# Led_panel_v2_0.net
KiCad netlist of a schematic drawn in EAGLE
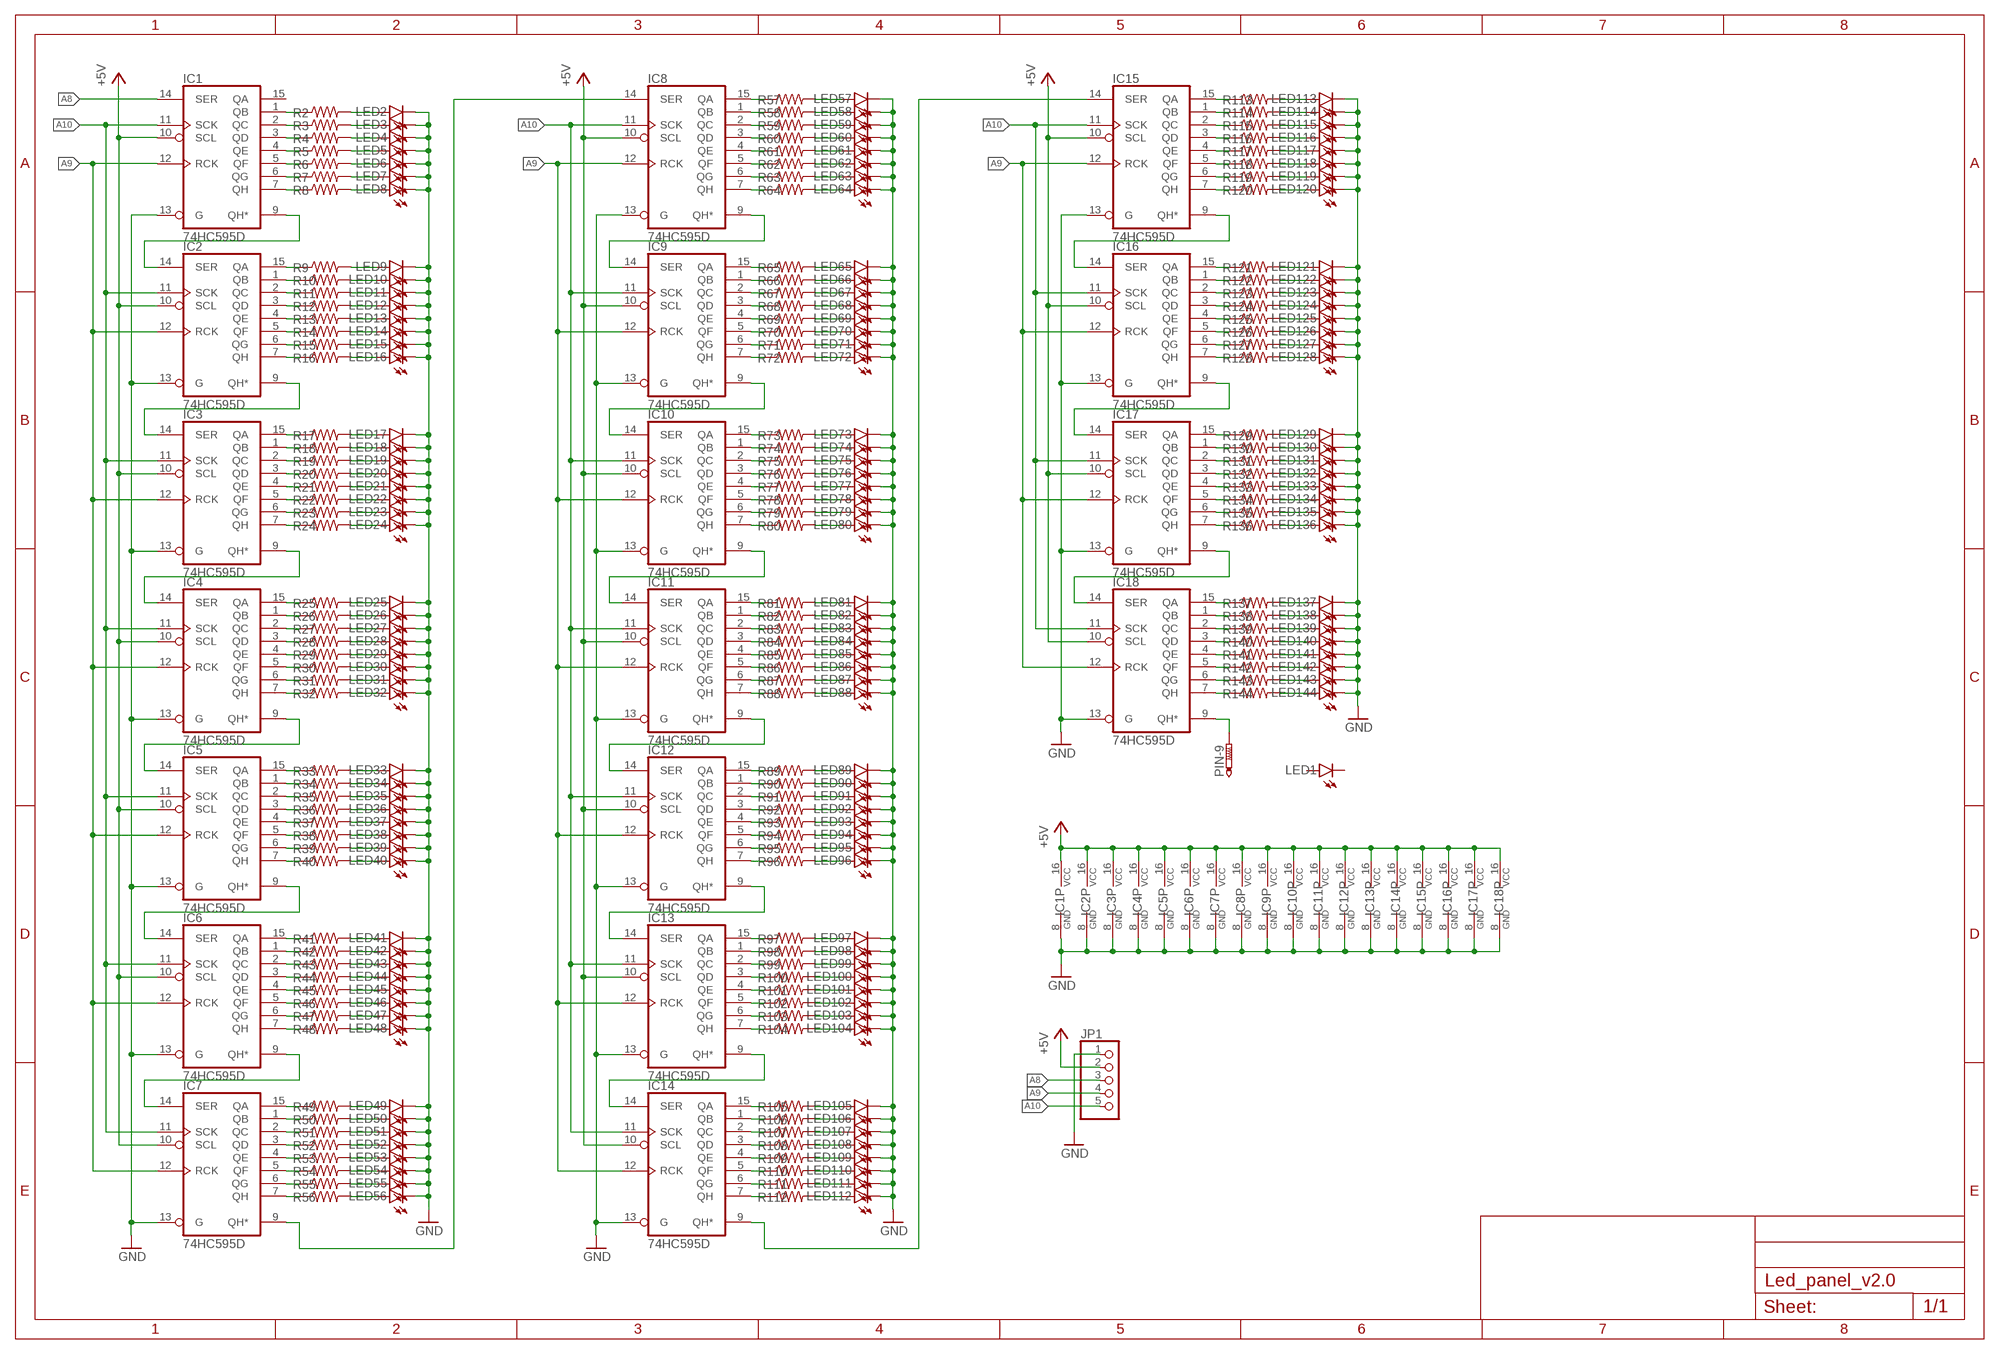
[diagram p0: schematic, sheet 1]

(export (version "E")
  (design (tool "Eeschema 10.0.6"))
  (components
    (comp (ref "IC1")
      (value "74HC595D")
      (footprint "eagle-import:SO16")
      (libsource (lib "eagle-import") (part "74595DHC"))
    )
    (comp (ref "IC2")
      (value "74HC595D")
      (footprint "eagle-import:SO16")
      (libsource (lib "eagle-import") (part "74595DHC"))
    )
    (comp (ref "IC3")
      (value "74HC595D")
      (footprint "eagle-import:SO16")
      (libsource (lib "eagle-import") (part "74595DHC"))
    )
    (comp (ref "IC4")
      (value "74HC595D")
      (footprint "eagle-import:SO16")
      (libsource (lib "eagle-import") (part "74595DHC"))
    )
    (comp (ref "IC5")
      (value "74HC595D")
      (footprint "eagle-import:SO16")
      (libsource (lib "eagle-import") (part "74595DHC"))
    )
    (comp (ref "IC6")
      (value "74HC595D")
      (footprint "eagle-import:SO16")
      (libsource (lib "eagle-import") (part "74595DHC"))
    )
    (comp (ref "IC7")
      (value "74HC595D")
      (footprint "eagle-import:SO16")
      (libsource (lib "eagle-import") (part "74595DHC"))
    )
    (comp (ref "IC8")
      (value "74HC595D")
      (footprint "eagle-import:SO16")
      (libsource (lib "eagle-import") (part "74595DHC"))
    )
    (comp (ref "IC9")
      (value "74HC595D")
      (footprint "eagle-import:SO16")
      (libsource (lib "eagle-import") (part "74595DHC"))
    )
    (comp (ref "IC10")
      (value "74HC595D")
      (footprint "eagle-import:SO16")
      (libsource (lib "eagle-import") (part "74595DHC"))
    )
    (comp (ref "IC11")
      (value "74HC595D")
      (footprint "eagle-import:SO16")
      (libsource (lib "eagle-import") (part "74595DHC"))
    )
    (comp (ref "IC12")
      (value "74HC595D")
      (footprint "eagle-import:SO16")
      (libsource (lib "eagle-import") (part "74595DHC"))
    )
    (comp (ref "IC13")
      (value "74HC595D")
      (footprint "eagle-import:SO16")
      (libsource (lib "eagle-import") (part "74595DHC"))
    )
    (comp (ref "IC14")
      (value "74HC595D")
      (footprint "eagle-import:SO16")
      (libsource (lib "eagle-import") (part "74595DHC"))
    )
    (comp (ref "IC15")
      (value "74HC595D")
      (footprint "eagle-import:SO16")
      (libsource (lib "eagle-import") (part "74595DHC"))
    )
    (comp (ref "IC16")
      (value "74HC595D")
      (footprint "eagle-import:SO16")
      (libsource (lib "eagle-import") (part "74595DHC"))
    )
    (comp (ref "IC17")
      (value "74HC595D")
      (footprint "eagle-import:SO16")
      (libsource (lib "eagle-import") (part "74595DHC"))
    )
    (comp (ref "IC18")
      (value "74HC595D")
      (footprint "eagle-import:SO16")
      (libsource (lib "eagle-import") (part "74595DHC"))
    )
    (comp (ref "JP1")
      (value "PINHD-1X5")
      (footprint "eagle-import:1X05")
      (libsource (lib "eagle-import") (part "PINHD-1X5"))
    )
    (comp (ref "LED1")
      (value "LED3MM")
      (footprint "eagle-import:LED3MM")
      (libsource (lib "eagle-import") (part "LED3MM"))
    )
    (comp (ref "LED2")
      (value "LED3MM")
      (footprint "eagle-import:LED3MM")
      (libsource (lib "eagle-import") (part "LED3MM"))
    )
    (comp (ref "LED3")
      (value "LED3MM")
      (footprint "eagle-import:LED3MM")
      (libsource (lib "eagle-import") (part "LED3MM"))
    )
    (comp (ref "LED4")
      (value "LED3MM")
      (footprint "eagle-import:LED3MM")
      (libsource (lib "eagle-import") (part "LED3MM"))
    )
    (comp (ref "LED5")
      (value "LED3MM")
      (footprint "eagle-import:LED3MM")
      (libsource (lib "eagle-import") (part "LED3MM"))
    )
    (comp (ref "LED6")
      (value "LED3MM")
      (footprint "eagle-import:LED3MM")
      (libsource (lib "eagle-import") (part "LED3MM"))
    )
    (comp (ref "LED7")
      (value "LED3MM")
      (footprint "eagle-import:LED3MM")
      (libsource (lib "eagle-import") (part "LED3MM"))
    )
    (comp (ref "LED8")
      (value "LED3MM")
      (footprint "eagle-import:LED3MM")
      (libsource (lib "eagle-import") (part "LED3MM"))
    )
    (comp (ref "LED9")
      (value "LED3MM")
      (footprint "eagle-import:LED3MM")
      (libsource (lib "eagle-import") (part "LED3MM"))
    )
    (comp (ref "LED10")
      (value "LED3MM")
      (footprint "eagle-import:LED3MM")
      (libsource (lib "eagle-import") (part "LED3MM"))
    )
    (comp (ref "LED11")
      (value "LED3MM")
      (footprint "eagle-import:LED3MM")
      (libsource (lib "eagle-import") (part "LED3MM"))
    )
    (comp (ref "LED12")
      (value "LED3MM")
      (footprint "eagle-import:LED3MM")
      (libsource (lib "eagle-import") (part "LED3MM"))
    )
    (comp (ref "LED13")
      (value "LED3MM")
      (footprint "eagle-import:LED3MM")
      (libsource (lib "eagle-import") (part "LED3MM"))
    )
    (comp (ref "LED14")
      (value "LED3MM")
      (footprint "eagle-import:LED3MM")
      (libsource (lib "eagle-import") (part "LED3MM"))
    )
    (comp (ref "LED15")
      (value "LED3MM")
      (footprint "eagle-import:LED3MM")
      (libsource (lib "eagle-import") (part "LED3MM"))
    )
    (comp (ref "LED16")
      (value "LED3MM")
      (footprint "eagle-import:LED3MM")
      (libsource (lib "eagle-import") (part "LED3MM"))
    )
    (comp (ref "LED17")
      (value "LED3MM")
      (footprint "eagle-import:LED3MM")
      (libsource (lib "eagle-import") (part "LED3MM"))
    )
    (comp (ref "LED18")
      (value "LED3MM")
      (footprint "eagle-import:LED3MM")
      (libsource (lib "eagle-import") (part "LED3MM"))
    )
    (comp (ref "LED19")
      (value "LED3MM")
      (footprint "eagle-import:LED3MM")
      (libsource (lib "eagle-import") (part "LED3MM"))
    )
    (comp (ref "LED20")
      (value "LED3MM")
      (footprint "eagle-import:LED3MM")
      (libsource (lib "eagle-import") (part "LED3MM"))
    )
    (comp (ref "LED21")
      (value "LED3MM")
      (footprint "eagle-import:LED3MM")
      (libsource (lib "eagle-import") (part "LED3MM"))
    )
    (comp (ref "LED22")
      (value "LED3MM")
      (footprint "eagle-import:LED3MM")
      (libsource (lib "eagle-import") (part "LED3MM"))
    )
    (comp (ref "LED23")
      (value "LED3MM")
      (footprint "eagle-import:LED3MM")
      (libsource (lib "eagle-import") (part "LED3MM"))
    )
    (comp (ref "LED24")
      (value "LED3MM")
      (footprint "eagle-import:LED3MM")
      (libsource (lib "eagle-import") (part "LED3MM"))
    )
    (comp (ref "LED25")
      (value "LED3MM")
      (footprint "eagle-import:LED3MM")
      (libsource (lib "eagle-import") (part "LED3MM"))
    )
    (comp (ref "LED26")
      (value "LED3MM")
      (footprint "eagle-import:LED3MM")
      (libsource (lib "eagle-import") (part "LED3MM"))
    )
    (comp (ref "LED27")
      (value "LED3MM")
      (footprint "eagle-import:LED3MM")
      (libsource (lib "eagle-import") (part "LED3MM"))
    )
    (comp (ref "LED28")
      (value "LED3MM")
      (footprint "eagle-import:LED3MM")
      (libsource (lib "eagle-import") (part "LED3MM"))
    )
    (comp (ref "LED29")
      (value "LED3MM")
      (footprint "eagle-import:LED3MM")
      (libsource (lib "eagle-import") (part "LED3MM"))
    )
    (comp (ref "LED30")
      (value "LED3MM")
      (footprint "eagle-import:LED3MM")
      (libsource (lib "eagle-import") (part "LED3MM"))
    )
    (comp (ref "LED31")
      (value "LED3MM")
      (footprint "eagle-import:LED3MM")
      (libsource (lib "eagle-import") (part "LED3MM"))
    )
    (comp (ref "LED32")
      (value "LED3MM")
      (footprint "eagle-import:LED3MM")
      (libsource (lib "eagle-import") (part "LED3MM"))
    )
    (comp (ref "LED33")
      (value "LED3MM")
      (footprint "eagle-import:LED3MM")
      (libsource (lib "eagle-import") (part "LED3MM"))
    )
    (comp (ref "LED34")
      (value "LED3MM")
      (footprint "eagle-import:LED3MM")
      (libsource (lib "eagle-import") (part "LED3MM"))
    )
    (comp (ref "LED35")
      (value "LED3MM")
      (footprint "eagle-import:LED3MM")
      (libsource (lib "eagle-import") (part "LED3MM"))
    )
    (comp (ref "LED36")
      (value "LED3MM")
      (footprint "eagle-import:LED3MM")
      (libsource (lib "eagle-import") (part "LED3MM"))
    )
    (comp (ref "LED37")
      (value "LED3MM")
      (footprint "eagle-import:LED3MM")
      (libsource (lib "eagle-import") (part "LED3MM"))
    )
    (comp (ref "LED38")
      (value "LED3MM")
      (footprint "eagle-import:LED3MM")
      (libsource (lib "eagle-import") (part "LED3MM"))
    )
    (comp (ref "LED39")
      (value "LED3MM")
      (footprint "eagle-import:LED3MM")
      (libsource (lib "eagle-import") (part "LED3MM"))
    )
    (comp (ref "LED40")
      (value "LED3MM")
      (footprint "eagle-import:LED3MM")
      (libsource (lib "eagle-import") (part "LED3MM"))
    )
    (comp (ref "LED41")
      (value "LED3MM")
      (footprint "eagle-import:LED3MM")
      (libsource (lib "eagle-import") (part "LED3MM"))
    )
    (comp (ref "LED42")
      (value "LED3MM")
      (footprint "eagle-import:LED3MM")
      (libsource (lib "eagle-import") (part "LED3MM"))
    )
    (comp (ref "LED43")
      (value "LED3MM")
      (footprint "eagle-import:LED3MM")
      (libsource (lib "eagle-import") (part "LED3MM"))
    )
    (comp (ref "LED44")
      (value "LED3MM")
      (footprint "eagle-import:LED3MM")
      (libsource (lib "eagle-import") (part "LED3MM"))
    )
    (comp (ref "LED45")
      (value "LED3MM")
      (footprint "eagle-import:LED3MM")
      (libsource (lib "eagle-import") (part "LED3MM"))
    )
    (comp (ref "LED46")
      (value "LED3MM")
      (footprint "eagle-import:LED3MM")
      (libsource (lib "eagle-import") (part "LED3MM"))
    )
    (comp (ref "LED47")
      (value "LED3MM")
      (footprint "eagle-import:LED3MM")
      (libsource (lib "eagle-import") (part "LED3MM"))
    )
    (comp (ref "LED48")
      (value "LED3MM")
      (footprint "eagle-import:LED3MM")
      (libsource (lib "eagle-import") (part "LED3MM"))
    )
    (comp (ref "LED49")
      (value "LED3MM")
      (footprint "eagle-import:LED3MM")
      (libsource (lib "eagle-import") (part "LED3MM"))
    )
    (comp (ref "LED50")
      (value "LED3MM")
      (footprint "eagle-import:LED3MM")
      (libsource (lib "eagle-import") (part "LED3MM"))
    )
    (comp (ref "LED51")
      (value "LED3MM")
      (footprint "eagle-import:LED3MM")
      (libsource (lib "eagle-import") (part "LED3MM"))
    )
    (comp (ref "LED52")
      (value "LED3MM")
      (footprint "eagle-import:LED3MM")
      (libsource (lib "eagle-import") (part "LED3MM"))
    )
    (comp (ref "LED53")
      (value "LED3MM")
      (footprint "eagle-import:LED3MM")
      (libsource (lib "eagle-import") (part "LED3MM"))
    )
    (comp (ref "LED54")
      (value "LED3MM")
      (footprint "eagle-import:LED3MM")
      (libsource (lib "eagle-import") (part "LED3MM"))
    )
    (comp (ref "LED55")
      (value "LED3MM")
      (footprint "eagle-import:LED3MM")
      (libsource (lib "eagle-import") (part "LED3MM"))
    )
    (comp (ref "LED56")
      (value "LED3MM")
      (footprint "eagle-import:LED3MM")
      (libsource (lib "eagle-import") (part "LED3MM"))
    )
    (comp (ref "LED57")
      (value "LED3MM")
      (footprint "eagle-import:LED3MM")
      (libsource (lib "eagle-import") (part "LED3MM"))
    )
    (comp (ref "LED58")
      (value "LED3MM")
      (footprint "eagle-import:LED3MM")
      (libsource (lib "eagle-import") (part "LED3MM"))
    )
    (comp (ref "LED59")
      (value "LED3MM")
      (footprint "eagle-import:LED3MM")
      (libsource (lib "eagle-import") (part "LED3MM"))
    )
    (comp (ref "LED60")
      (value "LED3MM")
      (footprint "eagle-import:LED3MM")
      (libsource (lib "eagle-import") (part "LED3MM"))
    )
    (comp (ref "LED61")
      (value "LED3MM")
      (footprint "eagle-import:LED3MM")
      (libsource (lib "eagle-import") (part "LED3MM"))
    )
    (comp (ref "LED62")
      (value "LED3MM")
      (footprint "eagle-import:LED3MM")
      (libsource (lib "eagle-import") (part "LED3MM"))
    )
    (comp (ref "LED63")
      (value "LED3MM")
      (footprint "eagle-import:LED3MM")
      (libsource (lib "eagle-import") (part "LED3MM"))
    )
    (comp (ref "LED64")
      (value "LED3MM")
      (footprint "eagle-import:LED3MM")
      (libsource (lib "eagle-import") (part "LED3MM"))
    )
    (comp (ref "LED65")
      (value "LED3MM")
      (footprint "eagle-import:LED3MM")
      (libsource (lib "eagle-import") (part "LED3MM"))
    )
    (comp (ref "LED66")
      (value "LED3MM")
      (footprint "eagle-import:LED3MM")
      (libsource (lib "eagle-import") (part "LED3MM"))
    )
    (comp (ref "LED67")
      (value "LED3MM")
      (footprint "eagle-import:LED3MM")
      (libsource (lib "eagle-import") (part "LED3MM"))
    )
    (comp (ref "LED68")
      (value "LED3MM")
      (footprint "eagle-import:LED3MM")
      (libsource (lib "eagle-import") (part "LED3MM"))
    )
    (comp (ref "LED69")
      (value "LED3MM")
      (footprint "eagle-import:LED3MM")
      (libsource (lib "eagle-import") (part "LED3MM"))
    )
    (comp (ref "LED70")
      (value "LED3MM")
      (footprint "eagle-import:LED3MM")
      (libsource (lib "eagle-import") (part "LED3MM"))
    )
    (comp (ref "LED71")
      (value "LED3MM")
      (footprint "eagle-import:LED3MM")
      (libsource (lib "eagle-import") (part "LED3MM"))
    )
    (comp (ref "LED72")
      (value "LED3MM")
      (footprint "eagle-import:LED3MM")
      (libsource (lib "eagle-import") (part "LED3MM"))
    )
    (comp (ref "LED73")
      (value "LED3MM")
      (footprint "eagle-import:LED3MM")
      (libsource (lib "eagle-import") (part "LED3MM"))
    )
    (comp (ref "LED74")
      (value "LED3MM")
      (footprint "eagle-import:LED3MM")
      (libsource (lib "eagle-import") (part "LED3MM"))
    )
    (comp (ref "LED75")
      (value "LED3MM")
      (footprint "eagle-import:LED3MM")
      (libsource (lib "eagle-import") (part "LED3MM"))
    )
    (comp (ref "LED76")
      (value "LED3MM")
      (footprint "eagle-import:LED3MM")
      (libsource (lib "eagle-import") (part "LED3MM"))
    )
    (comp (ref "LED77")
      (value "LED3MM")
      (footprint "eagle-import:LED3MM")
      (libsource (lib "eagle-import") (part "LED3MM"))
    )
    (comp (ref "LED78")
      (value "LED3MM")
      (footprint "eagle-import:LED3MM")
      (libsource (lib "eagle-import") (part "LED3MM"))
    )
    (comp (ref "LED79")
      (value "LED3MM")
      (footprint "eagle-import:LED3MM")
      (libsource (lib "eagle-import") (part "LED3MM"))
    )
    (comp (ref "LED80")
      (value "LED3MM")
      (footprint "eagle-import:LED3MM")
      (libsource (lib "eagle-import") (part "LED3MM"))
    )
    (comp (ref "LED81")
      (value "LED3MM")
      (footprint "eagle-import:LED3MM")
      (libsource (lib "eagle-import") (part "LED3MM"))
    )
    (comp (ref "LED82")
      (value "LED3MM")
      (footprint "eagle-import:LED3MM")
      (libsource (lib "eagle-import") (part "LED3MM"))
    )
    (comp (ref "LED83")
      (value "LED3MM")
      (footprint "eagle-import:LED3MM")
      (libsource (lib "eagle-import") (part "LED3MM"))
    )
    (comp (ref "LED84")
      (value "LED3MM")
      (footprint "eagle-import:LED3MM")
      (libsource (lib "eagle-import") (part "LED3MM"))
    )
    (comp (ref "LED85")
      (value "LED3MM")
      (footprint "eagle-import:LED3MM")
      (libsource (lib "eagle-import") (part "LED3MM"))
    )
    (comp (ref "LED86")
      (value "LED3MM")
      (footprint "eagle-import:LED3MM")
      (libsource (lib "eagle-import") (part "LED3MM"))
    )
    (comp (ref "LED87")
      (value "LED3MM")
      (footprint "eagle-import:LED3MM")
      (libsource (lib "eagle-import") (part "LED3MM"))
    )
    (comp (ref "LED88")
      (value "LED3MM")
      (footprint "eagle-import:LED3MM")
      (libsource (lib "eagle-import") (part "LED3MM"))
    )
    (comp (ref "LED89")
      (value "LED3MM")
      (footprint "eagle-import:LED3MM")
      (libsource (lib "eagle-import") (part "LED3MM"))
    )
    (comp (ref "LED90")
      (value "LED3MM")
      (footprint "eagle-import:LED3MM")
      (libsource (lib "eagle-import") (part "LED3MM"))
    )
    (comp (ref "LED91")
      (value "LED3MM")
      (footprint "eagle-import:LED3MM")
      (libsource (lib "eagle-import") (part "LED3MM"))
    )
    (comp (ref "LED92")
      (value "LED3MM")
      (footprint "eagle-import:LED3MM")
      (libsource (lib "eagle-import") (part "LED3MM"))
    )
    (comp (ref "LED93")
      (value "LED3MM")
      (footprint "eagle-import:LED3MM")
      (libsource (lib "eagle-import") (part "LED3MM"))
    )
    (comp (ref "LED94")
      (value "LED3MM")
      (footprint "eagle-import:LED3MM")
      (libsource (lib "eagle-import") (part "LED3MM"))
    )
    (comp (ref "LED95")
      (value "LED3MM")
      (footprint "eagle-import:LED3MM")
      (libsource (lib "eagle-import") (part "LED3MM"))
    )
    (comp (ref "LED96")
      (value "LED3MM")
      (footprint "eagle-import:LED3MM")
      (libsource (lib "eagle-import") (part "LED3MM"))
    )
    (comp (ref "LED97")
      (value "LED3MM")
      (footprint "eagle-import:LED3MM")
      (libsource (lib "eagle-import") (part "LED3MM"))
    )
    (comp (ref "LED98")
      (value "LED3MM")
      (footprint "eagle-import:LED3MM")
      (libsource (lib "eagle-import") (part "LED3MM"))
    )
    (comp (ref "LED99")
      (value "LED3MM")
      (footprint "eagle-import:LED3MM")
      (libsource (lib "eagle-import") (part "LED3MM"))
    )
    (comp (ref "LED100")
      (value "LED3MM")
      (footprint "eagle-import:LED3MM")
      (libsource (lib "eagle-import") (part "LED3MM"))
    )
    (comp (ref "LED101")
      (value "LED3MM")
      (footprint "eagle-import:LED3MM")
      (libsource (lib "eagle-import") (part "LED3MM"))
    )
    (comp (ref "LED102")
      (value "LED3MM")
      (footprint "eagle-import:LED3MM")
      (libsource (lib "eagle-import") (part "LED3MM"))
    )
    (comp (ref "LED103")
      (value "LED3MM")
      (footprint "eagle-import:LED3MM")
      (libsource (lib "eagle-import") (part "LED3MM"))
    )
    (comp (ref "LED104")
      (value "LED3MM")
      (footprint "eagle-import:LED3MM")
      (libsource (lib "eagle-import") (part "LED3MM"))
    )
    (comp (ref "LED105")
      (value "LED3MM")
      (footprint "eagle-import:LED3MM")
      (libsource (lib "eagle-import") (part "LED3MM"))
    )
    (comp (ref "LED106")
      (value "LED3MM")
      (footprint "eagle-import:LED3MM")
      (libsource (lib "eagle-import") (part "LED3MM"))
    )
    (comp (ref "LED107")
      (value "LED3MM")
      (footprint "eagle-import:LED3MM")
      (libsource (lib "eagle-import") (part "LED3MM"))
    )
    (comp (ref "LED108")
      (value "LED3MM")
      (footprint "eagle-import:LED3MM")
      (libsource (lib "eagle-import") (part "LED3MM"))
    )
    (comp (ref "LED109")
      (value "LED3MM")
      (footprint "eagle-import:LED3MM")
      (libsource (lib "eagle-import") (part "LED3MM"))
    )
    (comp (ref "LED110")
      (value "LED3MM")
      (footprint "eagle-import:LED3MM")
      (libsource (lib "eagle-import") (part "LED3MM"))
    )
    (comp (ref "LED111")
      (value "LED3MM")
      (footprint "eagle-import:LED3MM")
      (libsource (lib "eagle-import") (part "LED3MM"))
    )
    (comp (ref "LED112")
      (value "LED3MM")
      (footprint "eagle-import:LED3MM")
      (libsource (lib "eagle-import") (part "LED3MM"))
    )
    (comp (ref "LED113")
      (value "LED3MM")
      (footprint "eagle-import:LED3MM")
      (libsource (lib "eagle-import") (part "LED3MM"))
    )
    (comp (ref "LED114")
      (value "LED3MM")
      (footprint "eagle-import:LED3MM")
      (libsource (lib "eagle-import") (part "LED3MM"))
    )
    (comp (ref "LED115")
      (value "LED3MM")
      (footprint "eagle-import:LED3MM")
      (libsource (lib "eagle-import") (part "LED3MM"))
    )
    (comp (ref "LED116")
      (value "LED3MM")
      (footprint "eagle-import:LED3MM")
      (libsource (lib "eagle-import") (part "LED3MM"))
    )
    (comp (ref "LED117")
      (value "LED3MM")
      (footprint "eagle-import:LED3MM")
      (libsource (lib "eagle-import") (part "LED3MM"))
    )
    (comp (ref "LED118")
      (value "LED3MM")
      (footprint "eagle-import:LED3MM")
      (libsource (lib "eagle-import") (part "LED3MM"))
    )
    (comp (ref "LED119")
      (value "LED3MM")
      (footprint "eagle-import:LED3MM")
      (libsource (lib "eagle-import") (part "LED3MM"))
    )
    (comp (ref "LED120")
      (value "LED3MM")
      (footprint "eagle-import:LED3MM")
      (libsource (lib "eagle-import") (part "LED3MM"))
    )
    (comp (ref "LED121")
      (value "LED3MM")
      (footprint "eagle-import:LED3MM")
      (libsource (lib "eagle-import") (part "LED3MM"))
    )
    (comp (ref "LED122")
      (value "LED3MM")
      (footprint "eagle-import:LED3MM")
      (libsource (lib "eagle-import") (part "LED3MM"))
    )
    (comp (ref "LED123")
      (value "LED3MM")
      (footprint "eagle-import:LED3MM")
      (libsource (lib "eagle-import") (part "LED3MM"))
    )
    (comp (ref "LED124")
      (value "LED3MM")
      (footprint "eagle-import:LED3MM")
      (libsource (lib "eagle-import") (part "LED3MM"))
    )
    (comp (ref "LED125")
      (value "LED3MM")
      (footprint "eagle-import:LED3MM")
      (libsource (lib "eagle-import") (part "LED3MM"))
    )
    (comp (ref "LED126")
      (value "LED3MM")
      (footprint "eagle-import:LED3MM")
      (libsource (lib "eagle-import") (part "LED3MM"))
    )
    (comp (ref "LED127")
      (value "LED3MM")
      (footprint "eagle-import:LED3MM")
      (libsource (lib "eagle-import") (part "LED3MM"))
    )
    (comp (ref "LED128")
      (value "LED3MM")
      (footprint "eagle-import:LED3MM")
      (libsource (lib "eagle-import") (part "LED3MM"))
    )
    (comp (ref "LED129")
      (value "LED3MM")
      (footprint "eagle-import:LED3MM")
      (libsource (lib "eagle-import") (part "LED3MM"))
    )
    (comp (ref "LED130")
      (value "LED3MM")
      (footprint "eagle-import:LED3MM")
      (libsource (lib "eagle-import") (part "LED3MM"))
    )
    (comp (ref "LED131")
      (value "LED3MM")
      (footprint "eagle-import:LED3MM")
      (libsource (lib "eagle-import") (part "LED3MM"))
    )
    (comp (ref "LED132")
      (value "LED3MM")
      (footprint "eagle-import:LED3MM")
      (libsource (lib "eagle-import") (part "LED3MM"))
    )
    (comp (ref "LED133")
      (value "LED3MM")
      (footprint "eagle-import:LED3MM")
      (libsource (lib "eagle-import") (part "LED3MM"))
    )
    (comp (ref "LED134")
      (value "LED3MM")
      (footprint "eagle-import:LED3MM")
      (libsource (lib "eagle-import") (part "LED3MM"))
    )
    (comp (ref "LED135")
      (value "LED3MM")
      (footprint "eagle-import:LED3MM")
      (libsource (lib "eagle-import") (part "LED3MM"))
    )
    (comp (ref "LED136")
      (value "LED3MM")
      (footprint "eagle-import:LED3MM")
      (libsource (lib "eagle-import") (part "LED3MM"))
    )
    (comp (ref "LED137")
      (value "LED3MM")
      (footprint "eagle-import:LED3MM")
      (libsource (lib "eagle-import") (part "LED3MM"))
    )
    (comp (ref "LED138")
      (value "LED3MM")
      (footprint "eagle-import:LED3MM")
      (libsource (lib "eagle-import") (part "LED3MM"))
    )
    (comp (ref "LED139")
      (value "LED3MM")
      (footprint "eagle-import:LED3MM")
      (libsource (lib "eagle-import") (part "LED3MM"))
    )
    (comp (ref "LED140")
      (value "LED3MM")
      (footprint "eagle-import:LED3MM")
      (libsource (lib "eagle-import") (part "LED3MM"))
    )
    (comp (ref "LED141")
      (value "LED3MM")
      (footprint "eagle-import:LED3MM")
      (libsource (lib "eagle-import") (part "LED3MM"))
    )
    (comp (ref "LED142")
      (value "LED3MM")
      (footprint "eagle-import:LED3MM")
      (libsource (lib "eagle-import") (part "LED3MM"))
    )
    (comp (ref "LED143")
      (value "LED3MM")
      (footprint "eagle-import:LED3MM")
      (libsource (lib "eagle-import") (part "LED3MM"))
    )
    (comp (ref "LED144")
      (value "LED3MM")
      (footprint "eagle-import:LED3MM")
      (libsource (lib "eagle-import") (part "LED3MM"))
    )
    (comp (ref "PIN-9")
      (value "PTR1TP20R")
      (footprint "eagle-import:TP20R")
      (libsource (lib "eagle-import") (part "PTR1TP20R"))
    )
    (comp (ref "R2")
      (value "120R")
      (footprint "eagle-import:R0805")
      (libsource (lib "eagle-import") (part "R-US_R0805"))
    )
    (comp (ref "R3")
      (value "120R")
      (footprint "eagle-import:R0805")
      (libsource (lib "eagle-import") (part "R-US_R0805"))
    )
    (comp (ref "R4")
      (value "120R")
      (footprint "eagle-import:R0805")
      (libsource (lib "eagle-import") (part "R-US_R0805"))
    )
    (comp (ref "R5")
      (value "120R")
      (footprint "eagle-import:R0805")
      (libsource (lib "eagle-import") (part "R-US_R0805"))
    )
    (comp (ref "R6")
      (value "120R")
      (footprint "eagle-import:R0805")
      (libsource (lib "eagle-import") (part "R-US_R0805"))
    )
    (comp (ref "R7")
      (value "120R")
      (footprint "eagle-import:R0805")
      (libsource (lib "eagle-import") (part "R-US_R0805"))
    )
    (comp (ref "R8")
      (value "120R")
      (footprint "eagle-import:R0805")
      (libsource (lib "eagle-import") (part "R-US_R0805"))
    )
    (comp (ref "R9")
      (value "120R")
      (footprint "eagle-import:R0805")
      (libsource (lib "eagle-import") (part "R-US_R0805"))
    )
    (comp (ref "R10")
      (value "120R")
      (footprint "eagle-import:R0805")
      (libsource (lib "eagle-import") (part "R-US_R0805"))
    )
    (comp (ref "R11")
      (value "120R")
      (footprint "eagle-import:R0805")
      (libsource (lib "eagle-import") (part "R-US_R0805"))
    )
    (comp (ref "R12")
      (value "120R")
      (footprint "eagle-import:R0805")
      (libsource (lib "eagle-import") (part "R-US_R0805"))
    )
    (comp (ref "R13")
      (value "120R")
      (footprint "eagle-import:R0805")
      (libsource (lib "eagle-import") (part "R-US_R0805"))
    )
    (comp (ref "R14")
      (value "120R")
      (footprint "eagle-import:R0805")
      (libsource (lib "eagle-import") (part "R-US_R0805"))
    )
    (comp (ref "R15")
      (value "120R")
      (footprint "eagle-import:R0805")
      (libsource (lib "eagle-import") (part "R-US_R0805"))
    )
    (comp (ref "R16")
      (value "120R")
      (footprint "eagle-import:R0805")
      (libsource (lib "eagle-import") (part "R-US_R0805"))
    )
    (comp (ref "R17")
      (value "120R")
      (footprint "eagle-import:R0805")
      (libsource (lib "eagle-import") (part "R-US_R0805"))
    )
    (comp (ref "R18")
      (value "120R")
      (footprint "eagle-import:R0805")
      (libsource (lib "eagle-import") (part "R-US_R0805"))
    )
    (comp (ref "R19")
      (value "120R")
      (footprint "eagle-import:R0805")
      (libsource (lib "eagle-import") (part "R-US_R0805"))
    )
    (comp (ref "R20")
      (value "120R")
      (footprint "eagle-import:R0805")
      (libsource (lib "eagle-import") (part "R-US_R0805"))
    )
    (comp (ref "R21")
      (value "120R")
      (footprint "eagle-import:R0805")
      (libsource (lib "eagle-import") (part "R-US_R0805"))
    )
    (comp (ref "R22")
      (value "120R")
      (footprint "eagle-import:R0805")
      (libsource (lib "eagle-import") (part "R-US_R0805"))
    )
    (comp (ref "R23")
      (value "120R")
      (footprint "eagle-import:R0805")
      (libsource (lib "eagle-import") (part "R-US_R0805"))
    )
    (comp (ref "R24")
      (value "120R")
      (footprint "eagle-import:R0805")
      (libsource (lib "eagle-import") (part "R-US_R0805"))
    )
    (comp (ref "R25")
      (value "120R")
      (footprint "eagle-import:R0805")
      (libsource (lib "eagle-import") (part "R-US_R0805"))
    )
    (comp (ref "R26")
      (value "120R")
      (footprint "eagle-import:R0805")
      (libsource (lib "eagle-import") (part "R-US_R0805"))
    )
    (comp (ref "R27")
      (value "120R")
      (footprint "eagle-import:R0805")
      (libsource (lib "eagle-import") (part "R-US_R0805"))
    )
    (comp (ref "R28")
      (value "120R")
      (footprint "eagle-import:R0805")
      (libsource (lib "eagle-import") (part "R-US_R0805"))
    )
    (comp (ref "R29")
      (value "120R")
      (footprint "eagle-import:R0805")
      (libsource (lib "eagle-import") (part "R-US_R0805"))
    )
    (comp (ref "R30")
      (value "120R")
      (footprint "eagle-import:R0805")
      (libsource (lib "eagle-import") (part "R-US_R0805"))
    )
    (comp (ref "R31")
      (value "120R")
      (footprint "eagle-import:R0805")
      (libsource (lib "eagle-import") (part "R-US_R0805"))
    )
    (comp (ref "R32")
      (value "120R")
      (footprint "eagle-import:R0805")
      (libsource (lib "eagle-import") (part "R-US_R0805"))
    )
    (comp (ref "R33")
      (value "120R")
      (footprint "eagle-import:R0805")
      (libsource (lib "eagle-import") (part "R-US_R0805"))
    )
    (comp (ref "R34")
      (value "120R")
      (footprint "eagle-import:R0805")
      (libsource (lib "eagle-import") (part "R-US_R0805"))
    )
    (comp (ref "R35")
      (value "120R")
      (footprint "eagle-import:R0805")
      (libsource (lib "eagle-import") (part "R-US_R0805"))
    )
    (comp (ref "R36")
      (value "120R")
      (footprint "eagle-import:R0805")
      (libsource (lib "eagle-import") (part "R-US_R0805"))
    )
    (comp (ref "R37")
      (value "120R")
      (footprint "eagle-import:R0805")
      (libsource (lib "eagle-import") (part "R-US_R0805"))
    )
    (comp (ref "R38")
      (value "120R")
      (footprint "eagle-import:R0805")
      (libsource (lib "eagle-import") (part "R-US_R0805"))
    )
    (comp (ref "R39")
      (value "120R")
      (footprint "eagle-import:R0805")
      (libsource (lib "eagle-import") (part "R-US_R0805"))
    )
    (comp (ref "R40")
      (value "120R")
      (footprint "eagle-import:R0805")
      (libsource (lib "eagle-import") (part "R-US_R0805"))
    )
    (comp (ref "R41")
      (value "120R")
      (footprint "eagle-import:R0805")
      (libsource (lib "eagle-import") (part "R-US_R0805"))
    )
    (comp (ref "R42")
      (value "120R")
      (footprint "eagle-import:R0805")
      (libsource (lib "eagle-import") (part "R-US_R0805"))
    )
    (comp (ref "R43")
      (value "120R")
      (footprint "eagle-import:R0805")
      (libsource (lib "eagle-import") (part "R-US_R0805"))
    )
    (comp (ref "R44")
      (value "120R")
      (footprint "eagle-import:R0805")
      (libsource (lib "eagle-import") (part "R-US_R0805"))
    )
    (comp (ref "R45")
      (value "120R")
      (footprint "eagle-import:R0805")
      (libsource (lib "eagle-import") (part "R-US_R0805"))
    )
    (comp (ref "R46")
      (value "120R")
      (footprint "eagle-import:R0805")
      (libsource (lib "eagle-import") (part "R-US_R0805"))
    )
    (comp (ref "R47")
      (value "120R")
      (footprint "eagle-import:R0805")
      (libsource (lib "eagle-import") (part "R-US_R0805"))
    )
    (comp (ref "R48")
      (value "120R")
      (footprint "eagle-import:R0805")
      (libsource (lib "eagle-import") (part "R-US_R0805"))
    )
    (comp (ref "R49")
      (value "120R")
      (footprint "eagle-import:R0805")
      (libsource (lib "eagle-import") (part "R-US_R0805"))
    )
    (comp (ref "R50")
      (value "120R")
      (footprint "eagle-import:R0805")
      (libsource (lib "eagle-import") (part "R-US_R0805"))
    )
    (comp (ref "R51")
      (value "120R")
      (footprint "eagle-import:R0805")
      (libsource (lib "eagle-import") (part "R-US_R0805"))
    )
    (comp (ref "R52")
      (value "120R")
      (footprint "eagle-import:R0805")
      (libsource (lib "eagle-import") (part "R-US_R0805"))
    )
    (comp (ref "R53")
      (value "120R")
      (footprint "eagle-import:R0805")
      (libsource (lib "eagle-import") (part "R-US_R0805"))
    )
    (comp (ref "R54")
      (value "120R")
      (footprint "eagle-import:R0805")
      (libsource (lib "eagle-import") (part "R-US_R0805"))
    )
    (comp (ref "R55")
      (value "120R")
      (footprint "eagle-import:R0805")
      (libsource (lib "eagle-import") (part "R-US_R0805"))
    )
    (comp (ref "R56")
      (value "120R")
      (footprint "eagle-import:R0805")
      (libsource (lib "eagle-import") (part "R-US_R0805"))
    )
    (comp (ref "R57")
      (value "120R")
      (footprint "eagle-import:R0805")
      (libsource (lib "eagle-import") (part "R-US_R0805"))
    )
    (comp (ref "R58")
      (value "120R")
      (footprint "eagle-import:R0805")
      (libsource (lib "eagle-import") (part "R-US_R0805"))
    )
    (comp (ref "R59")
      (value "120R")
      (footprint "eagle-import:R0805")
      (libsource (lib "eagle-import") (part "R-US_R0805"))
    )
    (comp (ref "R60")
      (value "120R")
      (footprint "eagle-import:R0805")
      (libsource (lib "eagle-import") (part "R-US_R0805"))
    )
    (comp (ref "R61")
      (value "120R")
      (footprint "eagle-import:R0805")
      (libsource (lib "eagle-import") (part "R-US_R0805"))
    )
    (comp (ref "R62")
      (value "120R")
      (footprint "eagle-import:R0805")
      (libsource (lib "eagle-import") (part "R-US_R0805"))
    )
    (comp (ref "R63")
      (value "120R")
      (footprint "eagle-import:R0805")
      (libsource (lib "eagle-import") (part "R-US_R0805"))
    )
    (comp (ref "R64")
      (value "120R")
      (footprint "eagle-import:R0805")
      (libsource (lib "eagle-import") (part "R-US_R0805"))
    )
    (comp (ref "R65")
      (value "120R")
      (footprint "eagle-import:R0805")
      (libsource (lib "eagle-import") (part "R-US_R0805"))
    )
    (comp (ref "R66")
      (value "120R")
      (footprint "eagle-import:R0805")
      (libsource (lib "eagle-import") (part "R-US_R0805"))
    )
    (comp (ref "R67")
      (value "120R")
      (footprint "eagle-import:R0805")
      (libsource (lib "eagle-import") (part "R-US_R0805"))
    )
    (comp (ref "R68")
      (value "120R")
      (footprint "eagle-import:R0805")
      (libsource (lib "eagle-import") (part "R-US_R0805"))
    )
    (comp (ref "R69")
      (value "120R")
      (footprint "eagle-import:R0805")
      (libsource (lib "eagle-import") (part "R-US_R0805"))
    )
    (comp (ref "R70")
      (value "120R")
      (footprint "eagle-import:R0805")
      (libsource (lib "eagle-import") (part "R-US_R0805"))
    )
    (comp (ref "R71")
      (value "120R")
      (footprint "eagle-import:R0805")
      (libsource (lib "eagle-import") (part "R-US_R0805"))
    )
    (comp (ref "R72")
      (value "120R")
      (footprint "eagle-import:R0805")
      (libsource (lib "eagle-import") (part "R-US_R0805"))
    )
    (comp (ref "R73")
      (value "120R")
      (footprint "eagle-import:R0805")
      (libsource (lib "eagle-import") (part "R-US_R0805"))
    )
    (comp (ref "R74")
      (value "120R")
      (footprint "eagle-import:R0805")
      (libsource (lib "eagle-import") (part "R-US_R0805"))
    )
    (comp (ref "R75")
      (value "120R")
      (footprint "eagle-import:R0805")
      (libsource (lib "eagle-import") (part "R-US_R0805"))
    )
    (comp (ref "R76")
      (value "120R")
      (footprint "eagle-import:R0805")
      (libsource (lib "eagle-import") (part "R-US_R0805"))
    )
    (comp (ref "R77")
      (value "120R")
      (footprint "eagle-import:R0805")
      (libsource (lib "eagle-import") (part "R-US_R0805"))
    )
    (comp (ref "R78")
      (value "120R")
      (footprint "eagle-import:R0805")
      (libsource (lib "eagle-import") (part "R-US_R0805"))
    )
    (comp (ref "R79")
      (value "120R")
      (footprint "eagle-import:R0805")
      (libsource (lib "eagle-import") (part "R-US_R0805"))
    )
    (comp (ref "R80")
      (value "120R")
      (footprint "eagle-import:R0805")
      (libsource (lib "eagle-import") (part "R-US_R0805"))
    )
    (comp (ref "R81")
      (value "120R")
      (footprint "eagle-import:R0805")
      (libsource (lib "eagle-import") (part "R-US_R0805"))
    )
    (comp (ref "R82")
      (value "120R")
      (footprint "eagle-import:R0805")
      (libsource (lib "eagle-import") (part "R-US_R0805"))
    )
    (comp (ref "R83")
      (value "120R")
      (footprint "eagle-import:R0805")
      (libsource (lib "eagle-import") (part "R-US_R0805"))
    )
    (comp (ref "R84")
      (value "120R")
      (footprint "eagle-import:R0805")
      (libsource (lib "eagle-import") (part "R-US_R0805"))
    )
    (comp (ref "R85")
      (value "120R")
      (footprint "eagle-import:R0805")
      (libsource (lib "eagle-import") (part "R-US_R0805"))
    )
    (comp (ref "R86")
      (value "120R")
      (footprint "eagle-import:R0805")
      (libsource (lib "eagle-import") (part "R-US_R0805"))
    )
    (comp (ref "R87")
      (value "120R")
      (footprint "eagle-import:R0805")
      (libsource (lib "eagle-import") (part "R-US_R0805"))
    )
    (comp (ref "R88")
      (value "120R")
      (footprint "eagle-import:R0805")
      (libsource (lib "eagle-import") (part "R-US_R0805"))
    )
    (comp (ref "R89")
      (value "120R")
      (footprint "eagle-import:R0805")
      (libsource (lib "eagle-import") (part "R-US_R0805"))
    )
    (comp (ref "R90")
      (value "120R")
      (footprint "eagle-import:R0805")
      (libsource (lib "eagle-import") (part "R-US_R0805"))
    )
    (comp (ref "R91")
      (value "120R")
      (footprint "eagle-import:R0805")
      (libsource (lib "eagle-import") (part "R-US_R0805"))
    )
    (comp (ref "R92")
      (value "120R")
      (footprint "eagle-import:R0805")
      (libsource (lib "eagle-import") (part "R-US_R0805"))
    )
    (comp (ref "R93")
      (value "120R")
      (footprint "eagle-import:R0805")
      (libsource (lib "eagle-import") (part "R-US_R0805"))
    )
    (comp (ref "R94")
      (value "120R")
      (footprint "eagle-import:R0805")
      (libsource (lib "eagle-import") (part "R-US_R0805"))
    )
    (comp (ref "R95")
      (value "120R")
      (footprint "eagle-import:R0805")
      (libsource (lib "eagle-import") (part "R-US_R0805"))
    )
    (comp (ref "R96")
      (value "120R")
      (footprint "eagle-import:R0805")
      (libsource (lib "eagle-import") (part "R-US_R0805"))
    )
    (comp (ref "R97")
      (value "120R")
      (footprint "eagle-import:R0805")
      (libsource (lib "eagle-import") (part "R-US_R0805"))
    )
    (comp (ref "R98")
      (value "120R")
      (footprint "eagle-import:R0805")
      (libsource (lib "eagle-import") (part "R-US_R0805"))
    )
    (comp (ref "R99")
      (value "120R")
      (footprint "eagle-import:R0805")
      (libsource (lib "eagle-import") (part "R-US_R0805"))
    )
    (comp (ref "R100")
      (value "120R")
      (footprint "eagle-import:R0805")
      (libsource (lib "eagle-import") (part "R-US_R0805"))
    )
    (comp (ref "R101")
      (value "120R")
      (footprint "eagle-import:R0805")
      (libsource (lib "eagle-import") (part "R-US_R0805"))
    )
    (comp (ref "R102")
      (value "120R")
      (footprint "eagle-import:R0805")
      (libsource (lib "eagle-import") (part "R-US_R0805"))
    )
    (comp (ref "R103")
      (value "120R")
      (footprint "eagle-import:R0805")
      (libsource (lib "eagle-import") (part "R-US_R0805"))
    )
    (comp (ref "R104")
      (value "120R")
      (footprint "eagle-import:R0805")
      (libsource (lib "eagle-import") (part "R-US_R0805"))
    )
    (comp (ref "R105")
      (value "120R")
      (footprint "eagle-import:R0805")
      (libsource (lib "eagle-import") (part "R-US_R0805"))
    )
    (comp (ref "R106")
      (value "120R")
      (footprint "eagle-import:R0805")
      (libsource (lib "eagle-import") (part "R-US_R0805"))
    )
    (comp (ref "R107")
      (value "120R")
      (footprint "eagle-import:R0805")
      (libsource (lib "eagle-import") (part "R-US_R0805"))
    )
    (comp (ref "R108")
      (value "120R")
      (footprint "eagle-import:R0805")
      (libsource (lib "eagle-import") (part "R-US_R0805"))
    )
    (comp (ref "R109")
      (value "120R")
      (footprint "eagle-import:R0805")
      (libsource (lib "eagle-import") (part "R-US_R0805"))
    )
    (comp (ref "R110")
      (value "120R")
      (footprint "eagle-import:R0805")
      (libsource (lib "eagle-import") (part "R-US_R0805"))
    )
    (comp (ref "R111")
      (value "120R")
      (footprint "eagle-import:R0805")
      (libsource (lib "eagle-import") (part "R-US_R0805"))
    )
    (comp (ref "R112")
      (value "120R")
      (footprint "eagle-import:R0805")
      (libsource (lib "eagle-import") (part "R-US_R0805"))
    )
    (comp (ref "R113")
      (value "120R")
      (footprint "eagle-import:R0805")
      (libsource (lib "eagle-import") (part "R-US_R0805"))
    )
    (comp (ref "R114")
      (value "120R")
      (footprint "eagle-import:R0805")
      (libsource (lib "eagle-import") (part "R-US_R0805"))
    )
    (comp (ref "R115")
      (value "120R")
      (footprint "eagle-import:R0805")
      (libsource (lib "eagle-import") (part "R-US_R0805"))
    )
    (comp (ref "R116")
      (value "120R")
      (footprint "eagle-import:R0805")
      (libsource (lib "eagle-import") (part "R-US_R0805"))
    )
    (comp (ref "R117")
      (value "120R")
      (footprint "eagle-import:R0805")
      (libsource (lib "eagle-import") (part "R-US_R0805"))
    )
    (comp (ref "R118")
      (value "120R")
      (footprint "eagle-import:R0805")
      (libsource (lib "eagle-import") (part "R-US_R0805"))
    )
    (comp (ref "R119")
      (value "120R")
      (footprint "eagle-import:R0805")
      (libsource (lib "eagle-import") (part "R-US_R0805"))
    )
    (comp (ref "R120")
      (value "120R")
      (footprint "eagle-import:R0805")
      (libsource (lib "eagle-import") (part "R-US_R0805"))
    )
    (comp (ref "R121")
      (value "120R")
      (footprint "eagle-import:R0805")
      (libsource (lib "eagle-import") (part "R-US_R0805"))
    )
    (comp (ref "R122")
      (value "120R")
      (footprint "eagle-import:R0805")
      (libsource (lib "eagle-import") (part "R-US_R0805"))
    )
    (comp (ref "R123")
      (value "120R")
      (footprint "eagle-import:R0805")
      (libsource (lib "eagle-import") (part "R-US_R0805"))
    )
    (comp (ref "R124")
      (value "120R")
      (footprint "eagle-import:R0805")
      (libsource (lib "eagle-import") (part "R-US_R0805"))
    )
    (comp (ref "R125")
      (value "120R")
      (footprint "eagle-import:R0805")
      (libsource (lib "eagle-import") (part "R-US_R0805"))
    )
    (comp (ref "R126")
      (value "120R")
      (footprint "eagle-import:R0805")
      (libsource (lib "eagle-import") (part "R-US_R0805"))
    )
    (comp (ref "R127")
      (value "120R")
      (footprint "eagle-import:R0805")
      (libsource (lib "eagle-import") (part "R-US_R0805"))
    )
    (comp (ref "R128")
      (value "120R")
      (footprint "eagle-import:R0805")
      (libsource (lib "eagle-import") (part "R-US_R0805"))
    )
    (comp (ref "R129")
      (value "120R")
      (footprint "eagle-import:R0805")
      (libsource (lib "eagle-import") (part "R-US_R0805"))
    )
    (comp (ref "R130")
      (value "120R")
      (footprint "eagle-import:R0805")
      (libsource (lib "eagle-import") (part "R-US_R0805"))
    )
    (comp (ref "R131")
      (value "120R")
      (footprint "eagle-import:R0805")
      (libsource (lib "eagle-import") (part "R-US_R0805"))
    )
    (comp (ref "R132")
      (value "120R")
      (footprint "eagle-import:R0805")
      (libsource (lib "eagle-import") (part "R-US_R0805"))
    )
    (comp (ref "R133")
      (value "120R")
      (footprint "eagle-import:R0805")
      (libsource (lib "eagle-import") (part "R-US_R0805"))
    )
    (comp (ref "R134")
      (value "120R")
      (footprint "eagle-import:R0805")
      (libsource (lib "eagle-import") (part "R-US_R0805"))
    )
    (comp (ref "R135")
      (value "120R")
      (footprint "eagle-import:R0805")
      (libsource (lib "eagle-import") (part "R-US_R0805"))
    )
    (comp (ref "R136")
      (value "120R")
      (footprint "eagle-import:R0805")
      (libsource (lib "eagle-import") (part "R-US_R0805"))
    )
    (comp (ref "R137")
      (value "120R")
      (footprint "eagle-import:R0805")
      (libsource (lib "eagle-import") (part "R-US_R0805"))
    )
    (comp (ref "R138")
      (value "120R")
      (footprint "eagle-import:R0805")
      (libsource (lib "eagle-import") (part "R-US_R0805"))
    )
    (comp (ref "R139")
      (value "120R")
      (footprint "eagle-import:R0805")
      (libsource (lib "eagle-import") (part "R-US_R0805"))
    )
    (comp (ref "R140")
      (value "120R")
      (footprint "eagle-import:R0805")
      (libsource (lib "eagle-import") (part "R-US_R0805"))
    )
    (comp (ref "R141")
      (value "120R")
      (footprint "eagle-import:R0805")
      (libsource (lib "eagle-import") (part "R-US_R0805"))
    )
    (comp (ref "R142")
      (value "120R")
      (footprint "eagle-import:R0805")
      (libsource (lib "eagle-import") (part "R-US_R0805"))
    )
    (comp (ref "R143")
      (value "120R")
      (footprint "eagle-import:R0805")
      (libsource (lib "eagle-import") (part "R-US_R0805"))
    )
    (comp (ref "R144")
      (value "120R")
      (footprint "eagle-import:R0805")
      (libsource (lib "eagle-import") (part "R-US_R0805"))
    )
  )
  (nets
    (net (code "1") (name "+5V") (class "Default")
      (node (ref "IC1") (pin "10") (pinfunction "SCL_10") (pintype "input"))
      (node (ref "IC1") (pin "16") (pinfunction "VCC_16") (pintype "power_in"))
      (node (ref "IC10") (pin "10") (pinfunction "SCL_10") (pintype "input"))
      (node (ref "IC10") (pin "16") (pinfunction "VCC_16") (pintype "power_in"))
      (node (ref "IC11") (pin "10") (pinfunction "SCL_10") (pintype "input"))
      (node (ref "IC11") (pin "16") (pinfunction "VCC_16") (pintype "power_in"))
      (node (ref "IC12") (pin "10") (pinfunction "SCL_10") (pintype "input"))
      (node (ref "IC12") (pin "16") (pinfunction "VCC_16") (pintype "power_in"))
      (node (ref "IC13") (pin "10") (pinfunction "SCL_10") (pintype "input"))
      (node (ref "IC13") (pin "16") (pinfunction "VCC_16") (pintype "power_in"))
      (node (ref "IC14") (pin "10") (pinfunction "SCL_10") (pintype "input"))
      (node (ref "IC14") (pin "16") (pinfunction "VCC_16") (pintype "power_in"))
      (node (ref "IC15") (pin "10") (pinfunction "SCL_10") (pintype "input"))
      (node (ref "IC15") (pin "16") (pinfunction "VCC_16") (pintype "power_in"))
      (node (ref "IC16") (pin "10") (pinfunction "SCL_10") (pintype "input"))
      (node (ref "IC16") (pin "16") (pinfunction "VCC_16") (pintype "power_in"))
      (node (ref "IC17") (pin "10") (pinfunction "SCL_10") (pintype "input"))
      (node (ref "IC17") (pin "16") (pinfunction "VCC_16") (pintype "power_in"))
      (node (ref "IC18") (pin "10") (pinfunction "SCL_10") (pintype "input"))
      (node (ref "IC18") (pin "16") (pinfunction "VCC_16") (pintype "power_in"))
      (node (ref "IC2") (pin "10") (pinfunction "SCL_10") (pintype "input"))
      (node (ref "IC2") (pin "16") (pinfunction "VCC_16") (pintype "power_in"))
      (node (ref "IC3") (pin "10") (pinfunction "SCL_10") (pintype "input"))
      (node (ref "IC3") (pin "16") (pinfunction "VCC_16") (pintype "power_in"))
      (node (ref "IC4") (pin "10") (pinfunction "SCL_10") (pintype "input"))
      (node (ref "IC4") (pin "16") (pinfunction "VCC_16") (pintype "power_in"))
      (node (ref "IC5") (pin "10") (pinfunction "SCL_10") (pintype "input"))
      (node (ref "IC5") (pin "16") (pinfunction "VCC_16") (pintype "power_in"))
      (node (ref "IC6") (pin "10") (pinfunction "SCL_10") (pintype "input"))
      (node (ref "IC6") (pin "16") (pinfunction "VCC_16") (pintype "power_in"))
      (node (ref "IC7") (pin "10") (pinfunction "SCL_10") (pintype "input"))
      (node (ref "IC7") (pin "16") (pinfunction "VCC_16") (pintype "power_in"))
      (node (ref "IC8") (pin "10") (pinfunction "SCL_10") (pintype "input"))
      (node (ref "IC8") (pin "16") (pinfunction "VCC_16") (pintype "power_in"))
      (node (ref "IC9") (pin "10") (pinfunction "SCL_10") (pintype "input"))
      (node (ref "IC9") (pin "16") (pinfunction "VCC_16") (pintype "power_in"))
      (node (ref "JP1") (pin "2") (pinfunction "2_2") (pintype "passive"))
    )
    (net (code "2") (name "A8") (class "Default")
      (node (ref "IC1") (pin "14") (pinfunction "SER_14") (pintype "input"))
      (node (ref "JP1") (pin "3") (pinfunction "3_3") (pintype "passive"))
    )
    (net (code "3") (name "A9") (class "Default")
      (node (ref "IC1") (pin "12") (pinfunction "RCK_12") (pintype "input"))
      (node (ref "IC10") (pin "12") (pinfunction "RCK_12") (pintype "input"))
      (node (ref "IC11") (pin "12") (pinfunction "RCK_12") (pintype "input"))
      (node (ref "IC12") (pin "12") (pinfunction "RCK_12") (pintype "input"))
      (node (ref "IC13") (pin "12") (pinfunction "RCK_12") (pintype "input"))
      (node (ref "IC14") (pin "12") (pinfunction "RCK_12") (pintype "input"))
      (node (ref "IC15") (pin "12") (pinfunction "RCK_12") (pintype "input"))
      (node (ref "IC16") (pin "12") (pinfunction "RCK_12") (pintype "input"))
      (node (ref "IC17") (pin "12") (pinfunction "RCK_12") (pintype "input"))
      (node (ref "IC18") (pin "12") (pinfunction "RCK_12") (pintype "input"))
      (node (ref "IC2") (pin "12") (pinfunction "RCK_12") (pintype "input"))
      (node (ref "IC3") (pin "12") (pinfunction "RCK_12") (pintype "input"))
      (node (ref "IC4") (pin "12") (pinfunction "RCK_12") (pintype "input"))
      (node (ref "IC5") (pin "12") (pinfunction "RCK_12") (pintype "input"))
      (node (ref "IC6") (pin "12") (pinfunction "RCK_12") (pintype "input"))
      (node (ref "IC7") (pin "12") (pinfunction "RCK_12") (pintype "input"))
      (node (ref "IC8") (pin "12") (pinfunction "RCK_12") (pintype "input"))
      (node (ref "IC9") (pin "12") (pinfunction "RCK_12") (pintype "input"))
      (node (ref "JP1") (pin "4") (pinfunction "4_4") (pintype "passive"))
    )
    (net (code "4") (name "A10") (class "Default")
      (node (ref "IC1") (pin "11") (pinfunction "SCK_11") (pintype "input"))
      (node (ref "IC10") (pin "11") (pinfunction "SCK_11") (pintype "input"))
      (node (ref "IC11") (pin "11") (pinfunction "SCK_11") (pintype "input"))
      (node (ref "IC12") (pin "11") (pinfunction "SCK_11") (pintype "input"))
      (node (ref "IC13") (pin "11") (pinfunction "SCK_11") (pintype "input"))
      (node (ref "IC14") (pin "11") (pinfunction "SCK_11") (pintype "input"))
      (node (ref "IC15") (pin "11") (pinfunction "SCK_11") (pintype "input"))
      (node (ref "IC16") (pin "11") (pinfunction "SCK_11") (pintype "input"))
      (node (ref "IC17") (pin "11") (pinfunction "SCK_11") (pintype "input"))
      (node (ref "IC18") (pin "11") (pinfunction "SCK_11") (pintype "input"))
      (node (ref "IC2") (pin "11") (pinfunction "SCK_11") (pintype "input"))
      (node (ref "IC3") (pin "11") (pinfunction "SCK_11") (pintype "input"))
      (node (ref "IC4") (pin "11") (pinfunction "SCK_11") (pintype "input"))
      (node (ref "IC5") (pin "11") (pinfunction "SCK_11") (pintype "input"))
      (node (ref "IC6") (pin "11") (pinfunction "SCK_11") (pintype "input"))
      (node (ref "IC7") (pin "11") (pinfunction "SCK_11") (pintype "input"))
      (node (ref "IC8") (pin "11") (pinfunction "SCK_11") (pintype "input"))
      (node (ref "IC9") (pin "11") (pinfunction "SCK_11") (pintype "input"))
      (node (ref "JP1") (pin "5") (pinfunction "5_5") (pintype "passive"))
    )
    (net (code "5") (name "GND") (class "Default")
      (node (ref "IC1") (pin "13") (pinfunction "G_13") (pintype "input"))
      (node (ref "IC1") (pin "8") (pinfunction "GND_8") (pintype "power_in"))
      (node (ref "IC10") (pin "13") (pinfunction "G_13") (pintype "input"))
      (node (ref "IC10") (pin "8") (pinfunction "GND_8") (pintype "power_in"))
      (node (ref "IC11") (pin "13") (pinfunction "G_13") (pintype "input"))
      (node (ref "IC11") (pin "8") (pinfunction "GND_8") (pintype "power_in"))
      (node (ref "IC12") (pin "13") (pinfunction "G_13") (pintype "input"))
      (node (ref "IC12") (pin "8") (pinfunction "GND_8") (pintype "power_in"))
      (node (ref "IC13") (pin "13") (pinfunction "G_13") (pintype "input"))
      (node (ref "IC13") (pin "8") (pinfunction "GND_8") (pintype "power_in"))
      (node (ref "IC14") (pin "13") (pinfunction "G_13") (pintype "input"))
      (node (ref "IC14") (pin "8") (pinfunction "GND_8") (pintype "power_in"))
      (node (ref "IC15") (pin "13") (pinfunction "G_13") (pintype "input"))
      (node (ref "IC15") (pin "8") (pinfunction "GND_8") (pintype "power_in"))
      (node (ref "IC16") (pin "13") (pinfunction "G_13") (pintype "input"))
      (node (ref "IC16") (pin "8") (pinfunction "GND_8") (pintype "power_in"))
      (node (ref "IC17") (pin "13") (pinfunction "G_13") (pintype "input"))
      (node (ref "IC17") (pin "8") (pinfunction "GND_8") (pintype "power_in"))
      (node (ref "IC18") (pin "13") (pinfunction "G_13") (pintype "input"))
      (node (ref "IC18") (pin "8") (pinfunction "GND_8") (pintype "power_in"))
      (node (ref "IC2") (pin "13") (pinfunction "G_13") (pintype "input"))
      (node (ref "IC2") (pin "8") (pinfunction "GND_8") (pintype "power_in"))
      (node (ref "IC3") (pin "13") (pinfunction "G_13") (pintype "input"))
      (node (ref "IC3") (pin "8") (pinfunction "GND_8") (pintype "power_in"))
      (node (ref "IC4") (pin "13") (pinfunction "G_13") (pintype "input"))
      (node (ref "IC4") (pin "8") (pinfunction "GND_8") (pintype "power_in"))
      (node (ref "IC5") (pin "13") (pinfunction "G_13") (pintype "input"))
      (node (ref "IC5") (pin "8") (pinfunction "GND_8") (pintype "power_in"))
      (node (ref "IC6") (pin "13") (pinfunction "G_13") (pintype "input"))
      (node (ref "IC6") (pin "8") (pinfunction "GND_8") (pintype "power_in"))
      (node (ref "IC7") (pin "13") (pinfunction "G_13") (pintype "input"))
      (node (ref "IC7") (pin "8") (pinfunction "GND_8") (pintype "power_in"))
      (node (ref "IC8") (pin "13") (pinfunction "G_13") (pintype "input"))
      (node (ref "IC8") (pin "8") (pinfunction "GND_8") (pintype "power_in"))
      (node (ref "IC9") (pin "13") (pinfunction "G_13") (pintype "input"))
      (node (ref "IC9") (pin "8") (pinfunction "GND_8") (pintype "power_in"))
      (node (ref "JP1") (pin "1") (pinfunction "1_1") (pintype "passive"))
      (node (ref "LED10") (pin "K") (pinfunction "C_K") (pintype "passive"))
      (node (ref "LED100") (pin "K") (pinfunction "C_K") (pintype "passive"))
      (node (ref "LED101") (pin "K") (pinfunction "C_K") (pintype "passive"))
      (node (ref "LED102") (pin "K") (pinfunction "C_K") (pintype "passive"))
      (node (ref "LED103") (pin "K") (pinfunction "C_K") (pintype "passive"))
      (node (ref "LED104") (pin "K") (pinfunction "C_K") (pintype "passive"))
      (node (ref "LED105") (pin "K") (pinfunction "C_K") (pintype "passive"))
      (node (ref "LED106") (pin "K") (pinfunction "C_K") (pintype "passive"))
      (node (ref "LED107") (pin "K") (pinfunction "C_K") (pintype "passive"))
      (node (ref "LED108") (pin "K") (pinfunction "C_K") (pintype "passive"))
      (node (ref "LED109") (pin "K") (pinfunction "C_K") (pintype "passive"))
      (node (ref "LED11") (pin "K") (pinfunction "C_K") (pintype "passive"))
      (node (ref "LED110") (pin "K") (pinfunction "C_K") (pintype "passive"))
      (node (ref "LED111") (pin "K") (pinfunction "C_K") (pintype "passive"))
      (node (ref "LED112") (pin "K") (pinfunction "C_K") (pintype "passive"))
      (node (ref "LED113") (pin "K") (pinfunction "C_K") (pintype "passive"))
      (node (ref "LED114") (pin "K") (pinfunction "C_K") (pintype "passive"))
      (node (ref "LED115") (pin "K") (pinfunction "C_K") (pintype "passive"))
      (node (ref "LED116") (pin "K") (pinfunction "C_K") (pintype "passive"))
      (node (ref "LED117") (pin "K") (pinfunction "C_K") (pintype "passive"))
      (node (ref "LED118") (pin "K") (pinfunction "C_K") (pintype "passive"))
      (node (ref "LED119") (pin "K") (pinfunction "C_K") (pintype "passive"))
      (node (ref "LED12") (pin "K") (pinfunction "C_K") (pintype "passive"))
      (node (ref "LED120") (pin "K") (pinfunction "C_K") (pintype "passive"))
      (node (ref "LED121") (pin "K") (pinfunction "C_K") (pintype "passive"))
      (node (ref "LED122") (pin "K") (pinfunction "C_K") (pintype "passive"))
      (node (ref "LED123") (pin "K") (pinfunction "C_K") (pintype "passive"))
      (node (ref "LED124") (pin "K") (pinfunction "C_K") (pintype "passive"))
      (node (ref "LED125") (pin "K") (pinfunction "C_K") (pintype "passive"))
      (node (ref "LED126") (pin "K") (pinfunction "C_K") (pintype "passive"))
      (node (ref "LED127") (pin "K") (pinfunction "C_K") (pintype "passive"))
      (node (ref "LED128") (pin "K") (pinfunction "C_K") (pintype "passive"))
      (node (ref "LED129") (pin "K") (pinfunction "C_K") (pintype "passive"))
      (node (ref "LED13") (pin "K") (pinfunction "C_K") (pintype "passive"))
      (node (ref "LED130") (pin "K") (pinfunction "C_K") (pintype "passive"))
      (node (ref "LED131") (pin "K") (pinfunction "C_K") (pintype "passive"))
      (node (ref "LED132") (pin "K") (pinfunction "C_K") (pintype "passive"))
      (node (ref "LED133") (pin "K") (pinfunction "C_K") (pintype "passive"))
      (node (ref "LED134") (pin "K") (pinfunction "C_K") (pintype "passive"))
      (node (ref "LED135") (pin "K") (pinfunction "C_K") (pintype "passive"))
      (node (ref "LED136") (pin "K") (pinfunction "C_K") (pintype "passive"))
      (node (ref "LED137") (pin "K") (pinfunction "C_K") (pintype "passive"))
      (node (ref "LED138") (pin "K") (pinfunction "C_K") (pintype "passive"))
      (node (ref "LED139") (pin "K") (pinfunction "C_K") (pintype "passive"))
      (node (ref "LED14") (pin "K") (pinfunction "C_K") (pintype "passive"))
      (node (ref "LED140") (pin "K") (pinfunction "C_K") (pintype "passive"))
      (node (ref "LED141") (pin "K") (pinfunction "C_K") (pintype "passive"))
      (node (ref "LED142") (pin "K") (pinfunction "C_K") (pintype "passive"))
      (node (ref "LED143") (pin "K") (pinfunction "C_K") (pintype "passive"))
      (node (ref "LED144") (pin "K") (pinfunction "C_K") (pintype "passive"))
      (node (ref "LED15") (pin "K") (pinfunction "C_K") (pintype "passive"))
      (node (ref "LED16") (pin "K") (pinfunction "C_K") (pintype "passive"))
      (node (ref "LED17") (pin "K") (pinfunction "C_K") (pintype "passive"))
      (node (ref "LED18") (pin "K") (pinfunction "C_K") (pintype "passive"))
      (node (ref "LED19") (pin "K") (pinfunction "C_K") (pintype "passive"))
      (node (ref "LED2") (pin "K") (pinfunction "C_K") (pintype "passive"))
      (node (ref "LED20") (pin "K") (pinfunction "C_K") (pintype "passive"))
      (node (ref "LED21") (pin "K") (pinfunction "C_K") (pintype "passive"))
      (node (ref "LED22") (pin "K") (pinfunction "C_K") (pintype "passive"))
      (node (ref "LED23") (pin "K") (pinfunction "C_K") (pintype "passive"))
      (node (ref "LED24") (pin "K") (pinfunction "C_K") (pintype "passive"))
      (node (ref "LED25") (pin "K") (pinfunction "C_K") (pintype "passive"))
      (node (ref "LED26") (pin "K") (pinfunction "C_K") (pintype "passive"))
      (node (ref "LED27") (pin "K") (pinfunction "C_K") (pintype "passive"))
      (node (ref "LED28") (pin "K") (pinfunction "C_K") (pintype "passive"))
      (node (ref "LED29") (pin "K") (pinfunction "C_K") (pintype "passive"))
      (node (ref "LED3") (pin "K") (pinfunction "C_K") (pintype "passive"))
      (node (ref "LED30") (pin "K") (pinfunction "C_K") (pintype "passive"))
      (node (ref "LED31") (pin "K") (pinfunction "C_K") (pintype "passive"))
      (node (ref "LED32") (pin "K") (pinfunction "C_K") (pintype "passive"))
      (node (ref "LED33") (pin "K") (pinfunction "C_K") (pintype "passive"))
      (node (ref "LED34") (pin "K") (pinfunction "C_K") (pintype "passive"))
      (node (ref "LED35") (pin "K") (pinfunction "C_K") (pintype "passive"))
      (node (ref "LED36") (pin "K") (pinfunction "C_K") (pintype "passive"))
      (node (ref "LED37") (pin "K") (pinfunction "C_K") (pintype "passive"))
      (node (ref "LED38") (pin "K") (pinfunction "C_K") (pintype "passive"))
      (node (ref "LED39") (pin "K") (pinfunction "C_K") (pintype "passive"))
      (node (ref "LED4") (pin "K") (pinfunction "C_K") (pintype "passive"))
      (node (ref "LED40") (pin "K") (pinfunction "C_K") (pintype "passive"))
      (node (ref "LED41") (pin "K") (pinfunction "C_K") (pintype "passive"))
      (node (ref "LED42") (pin "K") (pinfunction "C_K") (pintype "passive"))
      (node (ref "LED43") (pin "K") (pinfunction "C_K") (pintype "passive"))
      (node (ref "LED44") (pin "K") (pinfunction "C_K") (pintype "passive"))
      (node (ref "LED45") (pin "K") (pinfunction "C_K") (pintype "passive"))
      (node (ref "LED46") (pin "K") (pinfunction "C_K") (pintype "passive"))
      (node (ref "LED47") (pin "K") (pinfunction "C_K") (pintype "passive"))
      (node (ref "LED48") (pin "K") (pinfunction "C_K") (pintype "passive"))
      (node (ref "LED49") (pin "K") (pinfunction "C_K") (pintype "passive"))
      (node (ref "LED5") (pin "K") (pinfunction "C_K") (pintype "passive"))
      (node (ref "LED50") (pin "K") (pinfunction "C_K") (pintype "passive"))
      (node (ref "LED51") (pin "K") (pinfunction "C_K") (pintype "passive"))
      (node (ref "LED52") (pin "K") (pinfunction "C_K") (pintype "passive"))
      (node (ref "LED53") (pin "K") (pinfunction "C_K") (pintype "passive"))
      (node (ref "LED54") (pin "K") (pinfunction "C_K") (pintype "passive"))
      (node (ref "LED55") (pin "K") (pinfunction "C_K") (pintype "passive"))
      (node (ref "LED56") (pin "K") (pinfunction "C_K") (pintype "passive"))
      (node (ref "LED57") (pin "K") (pinfunction "C_K") (pintype "passive"))
      (node (ref "LED58") (pin "K") (pinfunction "C_K") (pintype "passive"))
      (node (ref "LED59") (pin "K") (pinfunction "C_K") (pintype "passive"))
      (node (ref "LED6") (pin "K") (pinfunction "C_K") (pintype "passive"))
      (node (ref "LED60") (pin "K") (pinfunction "C_K") (pintype "passive"))
      (node (ref "LED61") (pin "K") (pinfunction "C_K") (pintype "passive"))
      (node (ref "LED62") (pin "K") (pinfunction "C_K") (pintype "passive"))
      (node (ref "LED63") (pin "K") (pinfunction "C_K") (pintype "passive"))
      (node (ref "LED64") (pin "K") (pinfunction "C_K") (pintype "passive"))
      (node (ref "LED65") (pin "K") (pinfunction "C_K") (pintype "passive"))
      (node (ref "LED66") (pin "K") (pinfunction "C_K") (pintype "passive"))
      (node (ref "LED67") (pin "K") (pinfunction "C_K") (pintype "passive"))
      (node (ref "LED68") (pin "K") (pinfunction "C_K") (pintype "passive"))
      (node (ref "LED69") (pin "K") (pinfunction "C_K") (pintype "passive"))
      (node (ref "LED7") (pin "K") (pinfunction "C_K") (pintype "passive"))
      (node (ref "LED70") (pin "K") (pinfunction "C_K") (pintype "passive"))
      (node (ref "LED71") (pin "K") (pinfunction "C_K") (pintype "passive"))
      (node (ref "LED72") (pin "K") (pinfunction "C_K") (pintype "passive"))
      (node (ref "LED73") (pin "K") (pinfunction "C_K") (pintype "passive"))
      (node (ref "LED74") (pin "K") (pinfunction "C_K") (pintype "passive"))
      (node (ref "LED75") (pin "K") (pinfunction "C_K") (pintype "passive"))
      (node (ref "LED76") (pin "K") (pinfunction "C_K") (pintype "passive"))
      (node (ref "LED77") (pin "K") (pinfunction "C_K") (pintype "passive"))
      (node (ref "LED78") (pin "K") (pinfunction "C_K") (pintype "passive"))
      (node (ref "LED79") (pin "K") (pinfunction "C_K") (pintype "passive"))
      (node (ref "LED8") (pin "K") (pinfunction "C_K") (pintype "passive"))
      (node (ref "LED80") (pin "K") (pinfunction "C_K") (pintype "passive"))
      (node (ref "LED81") (pin "K") (pinfunction "C_K") (pintype "passive"))
      (node (ref "LED82") (pin "K") (pinfunction "C_K") (pintype "passive"))
      (node (ref "LED83") (pin "K") (pinfunction "C_K") (pintype "passive"))
      (node (ref "LED84") (pin "K") (pinfunction "C_K") (pintype "passive"))
      (node (ref "LED85") (pin "K") (pinfunction "C_K") (pintype "passive"))
      (node (ref "LED86") (pin "K") (pinfunction "C_K") (pintype "passive"))
      (node (ref "LED87") (pin "K") (pinfunction "C_K") (pintype "passive"))
      (node (ref "LED88") (pin "K") (pinfunction "C_K") (pintype "passive"))
      (node (ref "LED89") (pin "K") (pinfunction "C_K") (pintype "passive"))
      (node (ref "LED9") (pin "K") (pinfunction "C_K") (pintype "passive"))
      (node (ref "LED90") (pin "K") (pinfunction "C_K") (pintype "passive"))
      (node (ref "LED91") (pin "K") (pinfunction "C_K") (pintype "passive"))
      (node (ref "LED92") (pin "K") (pinfunction "C_K") (pintype "passive"))
      (node (ref "LED93") (pin "K") (pinfunction "C_K") (pintype "passive"))
      (node (ref "LED94") (pin "K") (pinfunction "C_K") (pintype "passive"))
      (node (ref "LED95") (pin "K") (pinfunction "C_K") (pintype "passive"))
      (node (ref "LED96") (pin "K") (pinfunction "C_K") (pintype "passive"))
      (node (ref "LED97") (pin "K") (pinfunction "C_K") (pintype "passive"))
      (node (ref "LED98") (pin "K") (pinfunction "C_K") (pintype "passive"))
      (node (ref "LED99") (pin "K") (pinfunction "C_K") (pintype "passive"))
    )
    (net (code "6") (name "Net-(IC1A-QB)") (class "Default")
      (node (ref "IC1") (pin "1") (pinfunction "QB_1") (pintype "tri_state"))
      (node (ref "R2") (pin "1") (pinfunction "1_1") (pintype "passive"))
    )
    (net (code "7") (name "Net-(IC1A-QC)") (class "Default")
      (node (ref "IC1") (pin "2") (pinfunction "QC_2") (pintype "tri_state"))
      (node (ref "R3") (pin "1") (pinfunction "1_1") (pintype "passive"))
    )
    (net (code "8") (name "Net-(IC1A-QD)") (class "Default")
      (node (ref "IC1") (pin "3") (pinfunction "QD_3") (pintype "tri_state"))
      (node (ref "R4") (pin "1") (pinfunction "1_1") (pintype "passive"))
    )
    (net (code "9") (name "Net-(IC1A-QE)") (class "Default")
      (node (ref "IC1") (pin "4") (pinfunction "QE_4") (pintype "tri_state"))
      (node (ref "R5") (pin "1") (pinfunction "1_1") (pintype "passive"))
    )
    (net (code "10") (name "Net-(IC1A-QF)") (class "Default")
      (node (ref "IC1") (pin "5") (pinfunction "QF_5") (pintype "tri_state"))
      (node (ref "R6") (pin "1") (pinfunction "1_1") (pintype "passive"))
    )
    (net (code "11") (name "Net-(IC1A-QG)") (class "Default")
      (node (ref "IC1") (pin "6") (pinfunction "QG_6") (pintype "tri_state"))
      (node (ref "R7") (pin "1") (pinfunction "1_1") (pintype "passive"))
    )
    (net (code "12") (name "Net-(IC1A-QH)") (class "Default")
      (node (ref "IC1") (pin "7") (pinfunction "QH_7") (pintype "tri_state"))
      (node (ref "R8") (pin "1") (pinfunction "1_1") (pintype "passive"))
    )
    (net (code "13") (name "Net-(IC1A-QH*)") (class "Default")
      (node (ref "IC1") (pin "9") (pinfunction "QH*_9") (pintype "tri_state"))
      (node (ref "IC2") (pin "14") (pinfunction "SER_14") (pintype "input"))
    )
    (net (code "14") (name "Net-(IC2A-QA)") (class "Default")
      (node (ref "IC2") (pin "15") (pinfunction "QA_15") (pintype "tri_state"))
      (node (ref "R9") (pin "1") (pinfunction "1_1") (pintype "passive"))
    )
    (net (code "15") (name "Net-(IC2A-QB)") (class "Default")
      (node (ref "IC2") (pin "1") (pinfunction "QB_1") (pintype "tri_state"))
      (node (ref "R10") (pin "1") (pinfunction "1_1") (pintype "passive"))
    )
    (net (code "16") (name "Net-(IC2A-QC)") (class "Default")
      (node (ref "IC2") (pin "2") (pinfunction "QC_2") (pintype "tri_state"))
      (node (ref "R11") (pin "1") (pinfunction "1_1") (pintype "passive"))
    )
    (net (code "17") (name "Net-(IC2A-QD)") (class "Default")
      (node (ref "IC2") (pin "3") (pinfunction "QD_3") (pintype "tri_state"))
      (node (ref "R12") (pin "1") (pinfunction "1_1") (pintype "passive"))
    )
    (net (code "18") (name "Net-(IC2A-QE)") (class "Default")
      (node (ref "IC2") (pin "4") (pinfunction "QE_4") (pintype "tri_state"))
      (node (ref "R13") (pin "1") (pinfunction "1_1") (pintype "passive"))
    )
    (net (code "19") (name "Net-(IC2A-QF)") (class "Default")
      (node (ref "IC2") (pin "5") (pinfunction "QF_5") (pintype "tri_state"))
      (node (ref "R14") (pin "1") (pinfunction "1_1") (pintype "passive"))
    )
    (net (code "20") (name "Net-(IC2A-QG)") (class "Default")
      (node (ref "IC2") (pin "6") (pinfunction "QG_6") (pintype "tri_state"))
      (node (ref "R15") (pin "1") (pinfunction "1_1") (pintype "passive"))
    )
    (net (code "21") (name "Net-(IC2A-QH)") (class "Default")
      (node (ref "IC2") (pin "7") (pinfunction "QH_7") (pintype "tri_state"))
      (node (ref "R16") (pin "1") (pinfunction "1_1") (pintype "passive"))
    )
    (net (code "22") (name "Net-(IC2A-QH*)") (class "Default")
      (node (ref "IC2") (pin "9") (pinfunction "QH*_9") (pintype "tri_state"))
      (node (ref "IC3") (pin "14") (pinfunction "SER_14") (pintype "input"))
    )
    (net (code "23") (name "Net-(IC3A-QA)") (class "Default")
      (node (ref "IC3") (pin "15") (pinfunction "QA_15") (pintype "tri_state"))
      (node (ref "R17") (pin "1") (pinfunction "1_1") (pintype "passive"))
    )
    (net (code "24") (name "Net-(IC3A-QB)") (class "Default")
      (node (ref "IC3") (pin "1") (pinfunction "QB_1") (pintype "tri_state"))
      (node (ref "R18") (pin "1") (pinfunction "1_1") (pintype "passive"))
    )
    (net (code "25") (name "Net-(IC3A-QC)") (class "Default")
      (node (ref "IC3") (pin "2") (pinfunction "QC_2") (pintype "tri_state"))
      (node (ref "R19") (pin "1") (pinfunction "1_1") (pintype "passive"))
    )
    (net (code "26") (name "Net-(IC3A-QD)") (class "Default")
      (node (ref "IC3") (pin "3") (pinfunction "QD_3") (pintype "tri_state"))
      (node (ref "R20") (pin "1") (pinfunction "1_1") (pintype "passive"))
    )
    (net (code "27") (name "Net-(IC3A-QE)") (class "Default")
      (node (ref "IC3") (pin "4") (pinfunction "QE_4") (pintype "tri_state"))
      (node (ref "R21") (pin "1") (pinfunction "1_1") (pintype "passive"))
    )
    (net (code "28") (name "Net-(IC3A-QF)") (class "Default")
      (node (ref "IC3") (pin "5") (pinfunction "QF_5") (pintype "tri_state"))
      (node (ref "R22") (pin "1") (pinfunction "1_1") (pintype "passive"))
    )
    (net (code "29") (name "Net-(IC3A-QG)") (class "Default")
      (node (ref "IC3") (pin "6") (pinfunction "QG_6") (pintype "tri_state"))
      (node (ref "R23") (pin "1") (pinfunction "1_1") (pintype "passive"))
    )
    (net (code "30") (name "Net-(IC3A-QH)") (class "Default")
      (node (ref "IC3") (pin "7") (pinfunction "QH_7") (pintype "tri_state"))
      (node (ref "R24") (pin "1") (pinfunction "1_1") (pintype "passive"))
    )
    (net (code "31") (name "Net-(IC3A-QH*)") (class "Default")
      (node (ref "IC3") (pin "9") (pinfunction "QH*_9") (pintype "tri_state"))
      (node (ref "IC4") (pin "14") (pinfunction "SER_14") (pintype "input"))
    )
    (net (code "32") (name "Net-(IC4A-QA)") (class "Default")
      (node (ref "IC4") (pin "15") (pinfunction "QA_15") (pintype "tri_state"))
      (node (ref "R25") (pin "1") (pinfunction "1_1") (pintype "passive"))
    )
    (net (code "33") (name "Net-(IC4A-QB)") (class "Default")
      (node (ref "IC4") (pin "1") (pinfunction "QB_1") (pintype "tri_state"))
      (node (ref "R26") (pin "1") (pinfunction "1_1") (pintype "passive"))
    )
    (net (code "34") (name "Net-(IC4A-QC)") (class "Default")
      (node (ref "IC4") (pin "2") (pinfunction "QC_2") (pintype "tri_state"))
      (node (ref "R27") (pin "1") (pinfunction "1_1") (pintype "passive"))
    )
    (net (code "35") (name "Net-(IC4A-QD)") (class "Default")
      (node (ref "IC4") (pin "3") (pinfunction "QD_3") (pintype "tri_state"))
      (node (ref "R28") (pin "1") (pinfunction "1_1") (pintype "passive"))
    )
    (net (code "36") (name "Net-(IC4A-QE)") (class "Default")
      (node (ref "IC4") (pin "4") (pinfunction "QE_4") (pintype "tri_state"))
      (node (ref "R29") (pin "1") (pinfunction "1_1") (pintype "passive"))
    )
    (net (code "37") (name "Net-(IC4A-QF)") (class "Default")
      (node (ref "IC4") (pin "5") (pinfunction "QF_5") (pintype "tri_state"))
      (node (ref "R30") (pin "1") (pinfunction "1_1") (pintype "passive"))
    )
    (net (code "38") (name "Net-(IC4A-QG)") (class "Default")
      (node (ref "IC4") (pin "6") (pinfunction "QG_6") (pintype "tri_state"))
      (node (ref "R31") (pin "1") (pinfunction "1_1") (pintype "passive"))
    )
    (net (code "39") (name "Net-(IC4A-QH)") (class "Default")
      (node (ref "IC4") (pin "7") (pinfunction "QH_7") (pintype "tri_state"))
      (node (ref "R32") (pin "1") (pinfunction "1_1") (pintype "passive"))
    )
    (net (code "40") (name "Net-(IC4A-QH*)") (class "Default")
      (node (ref "IC4") (pin "9") (pinfunction "QH*_9") (pintype "tri_state"))
      (node (ref "IC5") (pin "14") (pinfunction "SER_14") (pintype "input"))
    )
    (net (code "41") (name "Net-(IC5A-QA)") (class "Default")
      (node (ref "IC5") (pin "15") (pinfunction "QA_15") (pintype "tri_state"))
      (node (ref "R33") (pin "1") (pinfunction "1_1") (pintype "passive"))
    )
    (net (code "42") (name "Net-(IC5A-QB)") (class "Default")
      (node (ref "IC5") (pin "1") (pinfunction "QB_1") (pintype "tri_state"))
      (node (ref "R34") (pin "1") (pinfunction "1_1") (pintype "passive"))
    )
    (net (code "43") (name "Net-(IC5A-QC)") (class "Default")
      (node (ref "IC5") (pin "2") (pinfunction "QC_2") (pintype "tri_state"))
      (node (ref "R35") (pin "1") (pinfunction "1_1") (pintype "passive"))
    )
    (net (code "44") (name "Net-(IC5A-QD)") (class "Default")
      (node (ref "IC5") (pin "3") (pinfunction "QD_3") (pintype "tri_state"))
      (node (ref "R36") (pin "1") (pinfunction "1_1") (pintype "passive"))
    )
    (net (code "45") (name "Net-(IC5A-QE)") (class "Default")
      (node (ref "IC5") (pin "4") (pinfunction "QE_4") (pintype "tri_state"))
      (node (ref "R37") (pin "1") (pinfunction "1_1") (pintype "passive"))
    )
    (net (code "46") (name "Net-(IC5A-QF)") (class "Default")
      (node (ref "IC5") (pin "5") (pinfunction "QF_5") (pintype "tri_state"))
      (node (ref "R38") (pin "1") (pinfunction "1_1") (pintype "passive"))
    )
    (net (code "47") (name "Net-(IC5A-QG)") (class "Default")
      (node (ref "IC5") (pin "6") (pinfunction "QG_6") (pintype "tri_state"))
      (node (ref "R39") (pin "1") (pinfunction "1_1") (pintype "passive"))
    )
    (net (code "48") (name "Net-(IC5A-QH)") (class "Default")
      (node (ref "IC5") (pin "7") (pinfunction "QH_7") (pintype "tri_state"))
      (node (ref "R40") (pin "1") (pinfunction "1_1") (pintype "passive"))
    )
    (net (code "49") (name "Net-(IC5A-QH*)") (class "Default")
      (node (ref "IC5") (pin "9") (pinfunction "QH*_9") (pintype "tri_state"))
      (node (ref "IC6") (pin "14") (pinfunction "SER_14") (pintype "input"))
    )
    (net (code "50") (name "Net-(IC6A-QA)") (class "Default")
      (node (ref "IC6") (pin "15") (pinfunction "QA_15") (pintype "tri_state"))
      (node (ref "R41") (pin "1") (pinfunction "1_1") (pintype "passive"))
    )
    (net (code "51") (name "Net-(IC6A-QB)") (class "Default")
      (node (ref "IC6") (pin "1") (pinfunction "QB_1") (pintype "tri_state"))
      (node (ref "R42") (pin "1") (pinfunction "1_1") (pintype "passive"))
    )
    (net (code "52") (name "Net-(IC6A-QC)") (class "Default")
      (node (ref "IC6") (pin "2") (pinfunction "QC_2") (pintype "tri_state"))
      (node (ref "R43") (pin "1") (pinfunction "1_1") (pintype "passive"))
    )
    (net (code "53") (name "Net-(IC6A-QD)") (class "Default")
      (node (ref "IC6") (pin "3") (pinfunction "QD_3") (pintype "tri_state"))
      (node (ref "R44") (pin "1") (pinfunction "1_1") (pintype "passive"))
    )
    (net (code "54") (name "Net-(IC6A-QE)") (class "Default")
      (node (ref "IC6") (pin "4") (pinfunction "QE_4") (pintype "tri_state"))
      (node (ref "R45") (pin "1") (pinfunction "1_1") (pintype "passive"))
    )
    (net (code "55") (name "Net-(IC6A-QF)") (class "Default")
      (node (ref "IC6") (pin "5") (pinfunction "QF_5") (pintype "tri_state"))
      (node (ref "R46") (pin "1") (pinfunction "1_1") (pintype "passive"))
    )
    (net (code "56") (name "Net-(IC6A-QG)") (class "Default")
      (node (ref "IC6") (pin "6") (pinfunction "QG_6") (pintype "tri_state"))
      (node (ref "R47") (pin "1") (pinfunction "1_1") (pintype "passive"))
    )
    (net (code "57") (name "Net-(IC6A-QH)") (class "Default")
      (node (ref "IC6") (pin "7") (pinfunction "QH_7") (pintype "tri_state"))
      (node (ref "R48") (pin "1") (pinfunction "1_1") (pintype "passive"))
    )
    (net (code "58") (name "Net-(IC6A-QH*)") (class "Default")
      (node (ref "IC6") (pin "9") (pinfunction "QH*_9") (pintype "tri_state"))
      (node (ref "IC7") (pin "14") (pinfunction "SER_14") (pintype "input"))
    )
    (net (code "59") (name "Net-(IC7A-QA)") (class "Default")
      (node (ref "IC7") (pin "15") (pinfunction "QA_15") (pintype "tri_state"))
      (node (ref "R49") (pin "1") (pinfunction "1_1") (pintype "passive"))
    )
    (net (code "60") (name "Net-(IC7A-QB)") (class "Default")
      (node (ref "IC7") (pin "1") (pinfunction "QB_1") (pintype "tri_state"))
      (node (ref "R50") (pin "1") (pinfunction "1_1") (pintype "passive"))
    )
    (net (code "61") (name "Net-(IC7A-QC)") (class "Default")
      (node (ref "IC7") (pin "2") (pinfunction "QC_2") (pintype "tri_state"))
      (node (ref "R51") (pin "1") (pinfunction "1_1") (pintype "passive"))
    )
    (net (code "62") (name "Net-(IC7A-QD)") (class "Default")
      (node (ref "IC7") (pin "3") (pinfunction "QD_3") (pintype "tri_state"))
      (node (ref "R52") (pin "1") (pinfunction "1_1") (pintype "passive"))
    )
    (net (code "63") (name "Net-(IC7A-QE)") (class "Default")
      (node (ref "IC7") (pin "4") (pinfunction "QE_4") (pintype "tri_state"))
      (node (ref "R53") (pin "1") (pinfunction "1_1") (pintype "passive"))
    )
    (net (code "64") (name "Net-(IC7A-QF)") (class "Default")
      (node (ref "IC7") (pin "5") (pinfunction "QF_5") (pintype "tri_state"))
      (node (ref "R54") (pin "1") (pinfunction "1_1") (pintype "passive"))
    )
    (net (code "65") (name "Net-(IC7A-QG)") (class "Default")
      (node (ref "IC7") (pin "6") (pinfunction "QG_6") (pintype "tri_state"))
      (node (ref "R55") (pin "1") (pinfunction "1_1") (pintype "passive"))
    )
    (net (code "66") (name "Net-(IC7A-QH)") (class "Default")
      (node (ref "IC7") (pin "7") (pinfunction "QH_7") (pintype "tri_state"))
      (node (ref "R56") (pin "1") (pinfunction "1_1") (pintype "passive"))
    )
    (net (code "67") (name "Net-(IC7A-QH*)") (class "Default")
      (node (ref "IC7") (pin "9") (pinfunction "QH*_9") (pintype "tri_state"))
      (node (ref "IC8") (pin "14") (pinfunction "SER_14") (pintype "input"))
    )
    (net (code "68") (name "Net-(IC8A-QA)") (class "Default")
      (node (ref "IC8") (pin "15") (pinfunction "QA_15") (pintype "tri_state"))
      (node (ref "R57") (pin "1") (pinfunction "1_1") (pintype "passive"))
    )
    (net (code "69") (name "Net-(IC8A-QB)") (class "Default")
      (node (ref "IC8") (pin "1") (pinfunction "QB_1") (pintype "tri_state"))
      (node (ref "R58") (pin "1") (pinfunction "1_1") (pintype "passive"))
    )
    (net (code "70") (name "Net-(IC8A-QC)") (class "Default")
      (node (ref "IC8") (pin "2") (pinfunction "QC_2") (pintype "tri_state"))
      (node (ref "R59") (pin "1") (pinfunction "1_1") (pintype "passive"))
    )
    (net (code "71") (name "Net-(IC8A-QD)") (class "Default")
      (node (ref "IC8") (pin "3") (pinfunction "QD_3") (pintype "tri_state"))
      (node (ref "R60") (pin "1") (pinfunction "1_1") (pintype "passive"))
    )
    (net (code "72") (name "Net-(IC8A-QE)") (class "Default")
      (node (ref "IC8") (pin "4") (pinfunction "QE_4") (pintype "tri_state"))
      (node (ref "R61") (pin "1") (pinfunction "1_1") (pintype "passive"))
    )
    (net (code "73") (name "Net-(IC8A-QF)") (class "Default")
      (node (ref "IC8") (pin "5") (pinfunction "QF_5") (pintype "tri_state"))
      (node (ref "R62") (pin "1") (pinfunction "1_1") (pintype "passive"))
    )
    (net (code "74") (name "Net-(IC8A-QG)") (class "Default")
      (node (ref "IC8") (pin "6") (pinfunction "QG_6") (pintype "tri_state"))
      (node (ref "R63") (pin "1") (pinfunction "1_1") (pintype "passive"))
    )
    (net (code "75") (name "Net-(IC8A-QH)") (class "Default")
      (node (ref "IC8") (pin "7") (pinfunction "QH_7") (pintype "tri_state"))
      (node (ref "R64") (pin "1") (pinfunction "1_1") (pintype "passive"))
    )
    (net (code "76") (name "Net-(IC8A-QH*)") (class "Default")
      (node (ref "IC8") (pin "9") (pinfunction "QH*_9") (pintype "tri_state"))
      (node (ref "IC9") (pin "14") (pinfunction "SER_14") (pintype "input"))
    )
    (net (code "77") (name "Net-(IC9A-QA)") (class "Default")
      (node (ref "IC9") (pin "15") (pinfunction "QA_15") (pintype "tri_state"))
      (node (ref "R65") (pin "1") (pinfunction "1_1") (pintype "passive"))
    )
    (net (code "78") (name "Net-(IC9A-QB)") (class "Default")
      (node (ref "IC9") (pin "1") (pinfunction "QB_1") (pintype "tri_state"))
      (node (ref "R66") (pin "1") (pinfunction "1_1") (pintype "passive"))
    )
    (net (code "79") (name "Net-(IC9A-QC)") (class "Default")
      (node (ref "IC9") (pin "2") (pinfunction "QC_2") (pintype "tri_state"))
      (node (ref "R67") (pin "1") (pinfunction "1_1") (pintype "passive"))
    )
    (net (code "80") (name "Net-(IC9A-QD)") (class "Default")
      (node (ref "IC9") (pin "3") (pinfunction "QD_3") (pintype "tri_state"))
      (node (ref "R68") (pin "1") (pinfunction "1_1") (pintype "passive"))
    )
    (net (code "81") (name "Net-(IC9A-QE)") (class "Default")
      (node (ref "IC9") (pin "4") (pinfunction "QE_4") (pintype "tri_state"))
      (node (ref "R69") (pin "1") (pinfunction "1_1") (pintype "passive"))
    )
    (net (code "82") (name "Net-(IC9A-QF)") (class "Default")
      (node (ref "IC9") (pin "5") (pinfunction "QF_5") (pintype "tri_state"))
      (node (ref "R70") (pin "1") (pinfunction "1_1") (pintype "passive"))
    )
    (net (code "83") (name "Net-(IC9A-QG)") (class "Default")
      (node (ref "IC9") (pin "6") (pinfunction "QG_6") (pintype "tri_state"))
      (node (ref "R71") (pin "1") (pinfunction "1_1") (pintype "passive"))
    )
    (net (code "84") (name "Net-(IC9A-QH)") (class "Default")
      (node (ref "IC9") (pin "7") (pinfunction "QH_7") (pintype "tri_state"))
      (node (ref "R72") (pin "1") (pinfunction "1_1") (pintype "passive"))
    )
    (net (code "85") (name "Net-(IC10A-QA)") (class "Default")
      (node (ref "IC10") (pin "15") (pinfunction "QA_15") (pintype "tri_state"))
      (node (ref "R73") (pin "1") (pinfunction "1_1") (pintype "passive"))
    )
    (net (code "86") (name "Net-(IC10A-QB)") (class "Default")
      (node (ref "IC10") (pin "1") (pinfunction "QB_1") (pintype "tri_state"))
      (node (ref "R74") (pin "1") (pinfunction "1_1") (pintype "passive"))
    )
    (net (code "87") (name "Net-(IC10A-QC)") (class "Default")
      (node (ref "IC10") (pin "2") (pinfunction "QC_2") (pintype "tri_state"))
      (node (ref "R75") (pin "1") (pinfunction "1_1") (pintype "passive"))
    )
    (net (code "88") (name "Net-(IC10A-QD)") (class "Default")
      (node (ref "IC10") (pin "3") (pinfunction "QD_3") (pintype "tri_state"))
      (node (ref "R76") (pin "1") (pinfunction "1_1") (pintype "passive"))
    )
    (net (code "89") (name "Net-(IC10A-QE)") (class "Default")
      (node (ref "IC10") (pin "4") (pinfunction "QE_4") (pintype "tri_state"))
      (node (ref "R77") (pin "1") (pinfunction "1_1") (pintype "passive"))
    )
    (net (code "90") (name "Net-(IC10A-QF)") (class "Default")
      (node (ref "IC10") (pin "5") (pinfunction "QF_5") (pintype "tri_state"))
      (node (ref "R78") (pin "1") (pinfunction "1_1") (pintype "passive"))
    )
    (net (code "91") (name "Net-(IC10A-QG)") (class "Default")
      (node (ref "IC10") (pin "6") (pinfunction "QG_6") (pintype "tri_state"))
      (node (ref "R79") (pin "1") (pinfunction "1_1") (pintype "passive"))
    )
    (net (code "92") (name "Net-(IC10A-QH)") (class "Default")
      (node (ref "IC10") (pin "7") (pinfunction "QH_7") (pintype "tri_state"))
      (node (ref "R80") (pin "1") (pinfunction "1_1") (pintype "passive"))
    )
    (net (code "93") (name "Net-(IC10A-QH*)") (class "Default")
      (node (ref "IC10") (pin "9") (pinfunction "QH*_9") (pintype "tri_state"))
      (node (ref "IC11") (pin "14") (pinfunction "SER_14") (pintype "input"))
    )
    (net (code "94") (name "Net-(IC10A-SER)") (class "Default")
      (node (ref "IC10") (pin "14") (pinfunction "SER_14") (pintype "input"))
      (node (ref "IC9") (pin "9") (pinfunction "QH*_9") (pintype "tri_state"))
    )
    (net (code "95") (name "Net-(IC11A-QA)") (class "Default")
      (node (ref "IC11") (pin "15") (pinfunction "QA_15") (pintype "tri_state"))
      (node (ref "R81") (pin "1") (pinfunction "1_1") (pintype "passive"))
    )
    (net (code "96") (name "Net-(IC11A-QB)") (class "Default")
      (node (ref "IC11") (pin "1") (pinfunction "QB_1") (pintype "tri_state"))
      (node (ref "R82") (pin "1") (pinfunction "1_1") (pintype "passive"))
    )
    (net (code "97") (name "Net-(IC11A-QC)") (class "Default")
      (node (ref "IC11") (pin "2") (pinfunction "QC_2") (pintype "tri_state"))
      (node (ref "R83") (pin "1") (pinfunction "1_1") (pintype "passive"))
    )
    (net (code "98") (name "Net-(IC11A-QD)") (class "Default")
      (node (ref "IC11") (pin "3") (pinfunction "QD_3") (pintype "tri_state"))
      (node (ref "R84") (pin "1") (pinfunction "1_1") (pintype "passive"))
    )
    (net (code "99") (name "Net-(IC11A-QE)") (class "Default")
      (node (ref "IC11") (pin "4") (pinfunction "QE_4") (pintype "tri_state"))
      (node (ref "R85") (pin "1") (pinfunction "1_1") (pintype "passive"))
    )
    (net (code "100") (name "Net-(IC11A-QF)") (class "Default")
      (node (ref "IC11") (pin "5") (pinfunction "QF_5") (pintype "tri_state"))
      (node (ref "R86") (pin "1") (pinfunction "1_1") (pintype "passive"))
    )
    (net (code "101") (name "Net-(IC11A-QG)") (class "Default")
      (node (ref "IC11") (pin "6") (pinfunction "QG_6") (pintype "tri_state"))
      (node (ref "R87") (pin "1") (pinfunction "1_1") (pintype "passive"))
    )
    (net (code "102") (name "Net-(IC11A-QH)") (class "Default")
      (node (ref "IC11") (pin "7") (pinfunction "QH_7") (pintype "tri_state"))
      (node (ref "R88") (pin "1") (pinfunction "1_1") (pintype "passive"))
    )
    (net (code "103") (name "Net-(IC11A-QH*)") (class "Default")
      (node (ref "IC11") (pin "9") (pinfunction "QH*_9") (pintype "tri_state"))
      (node (ref "IC12") (pin "14") (pinfunction "SER_14") (pintype "input"))
    )
    (net (code "104") (name "Net-(IC12A-QA)") (class "Default")
      (node (ref "IC12") (pin "15") (pinfunction "QA_15") (pintype "tri_state"))
      (node (ref "R89") (pin "1") (pinfunction "1_1") (pintype "passive"))
    )
    (net (code "105") (name "Net-(IC12A-QB)") (class "Default")
      (node (ref "IC12") (pin "1") (pinfunction "QB_1") (pintype "tri_state"))
      (node (ref "R90") (pin "1") (pinfunction "1_1") (pintype "passive"))
    )
    (net (code "106") (name "Net-(IC12A-QC)") (class "Default")
      (node (ref "IC12") (pin "2") (pinfunction "QC_2") (pintype "tri_state"))
      (node (ref "R91") (pin "1") (pinfunction "1_1") (pintype "passive"))
    )
    (net (code "107") (name "Net-(IC12A-QD)") (class "Default")
      (node (ref "IC12") (pin "3") (pinfunction "QD_3") (pintype "tri_state"))
      (node (ref "R92") (pin "1") (pinfunction "1_1") (pintype "passive"))
    )
    (net (code "108") (name "Net-(IC12A-QE)") (class "Default")
      (node (ref "IC12") (pin "4") (pinfunction "QE_4") (pintype "tri_state"))
      (node (ref "R93") (pin "1") (pinfunction "1_1") (pintype "passive"))
    )
    (net (code "109") (name "Net-(IC12A-QF)") (class "Default")
      (node (ref "IC12") (pin "5") (pinfunction "QF_5") (pintype "tri_state"))
      (node (ref "R94") (pin "1") (pinfunction "1_1") (pintype "passive"))
    )
    (net (code "110") (name "Net-(IC12A-QG)") (class "Default")
      (node (ref "IC12") (pin "6") (pinfunction "QG_6") (pintype "tri_state"))
      (node (ref "R95") (pin "1") (pinfunction "1_1") (pintype "passive"))
    )
    (net (code "111") (name "Net-(IC12A-QH)") (class "Default")
      (node (ref "IC12") (pin "7") (pinfunction "QH_7") (pintype "tri_state"))
      (node (ref "R96") (pin "1") (pinfunction "1_1") (pintype "passive"))
    )
    (net (code "112") (name "Net-(IC12A-QH*)") (class "Default")
      (node (ref "IC12") (pin "9") (pinfunction "QH*_9") (pintype "tri_state"))
      (node (ref "IC13") (pin "14") (pinfunction "SER_14") (pintype "input"))
    )
    (net (code "113") (name "Net-(IC13A-QA)") (class "Default")
      (node (ref "IC13") (pin "15") (pinfunction "QA_15") (pintype "tri_state"))
      (node (ref "R97") (pin "1") (pinfunction "1_1") (pintype "passive"))
    )
    (net (code "114") (name "Net-(IC13A-QB)") (class "Default")
      (node (ref "IC13") (pin "1") (pinfunction "QB_1") (pintype "tri_state"))
      (node (ref "R98") (pin "1") (pinfunction "1_1") (pintype "passive"))
    )
    (net (code "115") (name "Net-(IC13A-QC)") (class "Default")
      (node (ref "IC13") (pin "2") (pinfunction "QC_2") (pintype "tri_state"))
      (node (ref "R99") (pin "1") (pinfunction "1_1") (pintype "passive"))
    )
    (net (code "116") (name "Net-(IC13A-QD)") (class "Default")
      (node (ref "IC13") (pin "3") (pinfunction "QD_3") (pintype "tri_state"))
      (node (ref "R100") (pin "1") (pinfunction "1_1") (pintype "passive"))
    )
    (net (code "117") (name "Net-(IC13A-QE)") (class "Default")
      (node (ref "IC13") (pin "4") (pinfunction "QE_4") (pintype "tri_state"))
      (node (ref "R101") (pin "1") (pinfunction "1_1") (pintype "passive"))
    )
    (net (code "118") (name "Net-(IC13A-QF)") (class "Default")
      (node (ref "IC13") (pin "5") (pinfunction "QF_5") (pintype "tri_state"))
      (node (ref "R102") (pin "1") (pinfunction "1_1") (pintype "passive"))
    )
    (net (code "119") (name "Net-(IC13A-QG)") (class "Default")
      (node (ref "IC13") (pin "6") (pinfunction "QG_6") (pintype "tri_state"))
      (node (ref "R103") (pin "1") (pinfunction "1_1") (pintype "passive"))
    )
    (net (code "120") (name "Net-(IC13A-QH)") (class "Default")
      (node (ref "IC13") (pin "7") (pinfunction "QH_7") (pintype "tri_state"))
      (node (ref "R104") (pin "1") (pinfunction "1_1") (pintype "passive"))
    )
    (net (code "121") (name "Net-(IC13A-QH*)") (class "Default")
      (node (ref "IC13") (pin "9") (pinfunction "QH*_9") (pintype "tri_state"))
      (node (ref "IC14") (pin "14") (pinfunction "SER_14") (pintype "input"))
    )
    (net (code "122") (name "Net-(IC14A-QA)") (class "Default")
      (node (ref "IC14") (pin "15") (pinfunction "QA_15") (pintype "tri_state"))
      (node (ref "R105") (pin "1") (pinfunction "1_1") (pintype "passive"))
    )
    (net (code "123") (name "Net-(IC14A-QB)") (class "Default")
      (node (ref "IC14") (pin "1") (pinfunction "QB_1") (pintype "tri_state"))
      (node (ref "R106") (pin "1") (pinfunction "1_1") (pintype "passive"))
    )
    (net (code "124") (name "Net-(IC14A-QC)") (class "Default")
      (node (ref "IC14") (pin "2") (pinfunction "QC_2") (pintype "tri_state"))
      (node (ref "R107") (pin "1") (pinfunction "1_1") (pintype "passive"))
    )
    (net (code "125") (name "Net-(IC14A-QD)") (class "Default")
      (node (ref "IC14") (pin "3") (pinfunction "QD_3") (pintype "tri_state"))
      (node (ref "R108") (pin "1") (pinfunction "1_1") (pintype "passive"))
    )
    (net (code "126") (name "Net-(IC14A-QE)") (class "Default")
      (node (ref "IC14") (pin "4") (pinfunction "QE_4") (pintype "tri_state"))
      (node (ref "R109") (pin "1") (pinfunction "1_1") (pintype "passive"))
    )
    (net (code "127") (name "Net-(IC14A-QF)") (class "Default")
      (node (ref "IC14") (pin "5") (pinfunction "QF_5") (pintype "tri_state"))
      (node (ref "R110") (pin "1") (pinfunction "1_1") (pintype "passive"))
    )
    (net (code "128") (name "Net-(IC14A-QG)") (class "Default")
      (node (ref "IC14") (pin "6") (pinfunction "QG_6") (pintype "tri_state"))
      (node (ref "R111") (pin "1") (pinfunction "1_1") (pintype "passive"))
    )
    (net (code "129") (name "Net-(IC14A-QH)") (class "Default")
      (node (ref "IC14") (pin "7") (pinfunction "QH_7") (pintype "tri_state"))
      (node (ref "R112") (pin "1") (pinfunction "1_1") (pintype "passive"))
    )
    (net (code "130") (name "Net-(IC14A-QH*)") (class "Default")
      (node (ref "IC14") (pin "9") (pinfunction "QH*_9") (pintype "tri_state"))
      (node (ref "IC15") (pin "14") (pinfunction "SER_14") (pintype "input"))
    )
    (net (code "131") (name "Net-(IC15A-QA)") (class "Default")
      (node (ref "IC15") (pin "15") (pinfunction "QA_15") (pintype "tri_state"))
      (node (ref "R113") (pin "1") (pinfunction "1_1") (pintype "passive"))
    )
    (net (code "132") (name "Net-(IC15A-QB)") (class "Default")
      (node (ref "IC15") (pin "1") (pinfunction "QB_1") (pintype "tri_state"))
      (node (ref "R114") (pin "1") (pinfunction "1_1") (pintype "passive"))
    )
    (net (code "133") (name "Net-(IC15A-QC)") (class "Default")
      (node (ref "IC15") (pin "2") (pinfunction "QC_2") (pintype "tri_state"))
      (node (ref "R115") (pin "1") (pinfunction "1_1") (pintype "passive"))
    )
    (net (code "134") (name "Net-(IC15A-QD)") (class "Default")
      (node (ref "IC15") (pin "3") (pinfunction "QD_3") (pintype "tri_state"))
      (node (ref "R116") (pin "1") (pinfunction "1_1") (pintype "passive"))
    )
    (net (code "135") (name "Net-(IC15A-QE)") (class "Default")
      (node (ref "IC15") (pin "4") (pinfunction "QE_4") (pintype "tri_state"))
      (node (ref "R117") (pin "1") (pinfunction "1_1") (pintype "passive"))
    )
    (net (code "136") (name "Net-(IC15A-QF)") (class "Default")
      (node (ref "IC15") (pin "5") (pinfunction "QF_5") (pintype "tri_state"))
      (node (ref "R118") (pin "1") (pinfunction "1_1") (pintype "passive"))
    )
    (net (code "137") (name "Net-(IC15A-QG)") (class "Default")
      (node (ref "IC15") (pin "6") (pinfunction "QG_6") (pintype "tri_state"))
      (node (ref "R119") (pin "1") (pinfunction "1_1") (pintype "passive"))
    )
    (net (code "138") (name "Net-(IC15A-QH)") (class "Default")
      (node (ref "IC15") (pin "7") (pinfunction "QH_7") (pintype "tri_state"))
      (node (ref "R120") (pin "1") (pinfunction "1_1") (pintype "passive"))
    )
    (net (code "139") (name "Net-(IC15A-QH*)") (class "Default")
      (node (ref "IC15") (pin "9") (pinfunction "QH*_9") (pintype "tri_state"))
      (node (ref "IC16") (pin "14") (pinfunction "SER_14") (pintype "input"))
    )
    (net (code "140") (name "Net-(IC16A-QA)") (class "Default")
      (node (ref "IC16") (pin "15") (pinfunction "QA_15") (pintype "tri_state"))
      (node (ref "R121") (pin "1") (pinfunction "1_1") (pintype "passive"))
    )
    (net (code "141") (name "Net-(IC16A-QB)") (class "Default")
      (node (ref "IC16") (pin "1") (pinfunction "QB_1") (pintype "tri_state"))
      (node (ref "R122") (pin "1") (pinfunction "1_1") (pintype "passive"))
    )
    (net (code "142") (name "Net-(IC16A-QC)") (class "Default")
      (node (ref "IC16") (pin "2") (pinfunction "QC_2") (pintype "tri_state"))
      (node (ref "R123") (pin "1") (pinfunction "1_1") (pintype "passive"))
    )
    (net (code "143") (name "Net-(IC16A-QD)") (class "Default")
      (node (ref "IC16") (pin "3") (pinfunction "QD_3") (pintype "tri_state"))
      (node (ref "R124") (pin "1") (pinfunction "1_1") (pintype "passive"))
    )
    (net (code "144") (name "Net-(IC16A-QE)") (class "Default")
      (node (ref "IC16") (pin "4") (pinfunction "QE_4") (pintype "tri_state"))
      (node (ref "R125") (pin "1") (pinfunction "1_1") (pintype "passive"))
    )
    (net (code "145") (name "Net-(IC16A-QF)") (class "Default")
      (node (ref "IC16") (pin "5") (pinfunction "QF_5") (pintype "tri_state"))
      (node (ref "R126") (pin "1") (pinfunction "1_1") (pintype "passive"))
    )
    (net (code "146") (name "Net-(IC16A-QG)") (class "Default")
      (node (ref "IC16") (pin "6") (pinfunction "QG_6") (pintype "tri_state"))
      (node (ref "R127") (pin "1") (pinfunction "1_1") (pintype "passive"))
    )
    (net (code "147") (name "Net-(IC16A-QH)") (class "Default")
      (node (ref "IC16") (pin "7") (pinfunction "QH_7") (pintype "tri_state"))
      (node (ref "R128") (pin "1") (pinfunction "1_1") (pintype "passive"))
    )
    (net (code "148") (name "Net-(IC16A-QH*)") (class "Default")
      (node (ref "IC16") (pin "9") (pinfunction "QH*_9") (pintype "tri_state"))
      (node (ref "IC17") (pin "14") (pinfunction "SER_14") (pintype "input"))
    )
    (net (code "149") (name "Net-(IC17A-QA)") (class "Default")
      (node (ref "IC17") (pin "15") (pinfunction "QA_15") (pintype "tri_state"))
      (node (ref "R129") (pin "1") (pinfunction "1_1") (pintype "passive"))
    )
    (net (code "150") (name "Net-(IC17A-QB)") (class "Default")
      (node (ref "IC17") (pin "1") (pinfunction "QB_1") (pintype "tri_state"))
      (node (ref "R130") (pin "1") (pinfunction "1_1") (pintype "passive"))
    )
    (net (code "151") (name "Net-(IC17A-QC)") (class "Default")
      (node (ref "IC17") (pin "2") (pinfunction "QC_2") (pintype "tri_state"))
      (node (ref "R131") (pin "1") (pinfunction "1_1") (pintype "passive"))
    )
    (net (code "152") (name "Net-(IC17A-QD)") (class "Default")
      (node (ref "IC17") (pin "3") (pinfunction "QD_3") (pintype "tri_state"))
      (node (ref "R132") (pin "1") (pinfunction "1_1") (pintype "passive"))
    )
    (net (code "153") (name "Net-(IC17A-QE)") (class "Default")
      (node (ref "IC17") (pin "4") (pinfunction "QE_4") (pintype "tri_state"))
      (node (ref "R133") (pin "1") (pinfunction "1_1") (pintype "passive"))
    )
    (net (code "154") (name "Net-(IC17A-QF)") (class "Default")
      (node (ref "IC17") (pin "5") (pinfunction "QF_5") (pintype "tri_state"))
      (node (ref "R134") (pin "1") (pinfunction "1_1") (pintype "passive"))
    )
    (net (code "155") (name "Net-(IC17A-QG)") (class "Default")
      (node (ref "IC17") (pin "6") (pinfunction "QG_6") (pintype "tri_state"))
      (node (ref "R135") (pin "1") (pinfunction "1_1") (pintype "passive"))
    )
    (net (code "156") (name "Net-(IC17A-QH)") (class "Default")
      (node (ref "IC17") (pin "7") (pinfunction "QH_7") (pintype "tri_state"))
      (node (ref "R136") (pin "1") (pinfunction "1_1") (pintype "passive"))
    )
    (net (code "157") (name "Net-(IC17A-QH*)") (class "Default")
      (node (ref "IC17") (pin "9") (pinfunction "QH*_9") (pintype "tri_state"))
      (node (ref "IC18") (pin "14") (pinfunction "SER_14") (pintype "input"))
    )
    (net (code "158") (name "Net-(IC18A-QA)") (class "Default")
      (node (ref "IC18") (pin "15") (pinfunction "QA_15") (pintype "tri_state"))
      (node (ref "R137") (pin "1") (pinfunction "1_1") (pintype "passive"))
    )
    (net (code "159") (name "Net-(IC18A-QB)") (class "Default")
      (node (ref "IC18") (pin "1") (pinfunction "QB_1") (pintype "tri_state"))
      (node (ref "R138") (pin "1") (pinfunction "1_1") (pintype "passive"))
    )
    (net (code "160") (name "Net-(IC18A-QC)") (class "Default")
      (node (ref "IC18") (pin "2") (pinfunction "QC_2") (pintype "tri_state"))
      (node (ref "R139") (pin "1") (pinfunction "1_1") (pintype "passive"))
    )
    (net (code "161") (name "Net-(IC18A-QD)") (class "Default")
      (node (ref "IC18") (pin "3") (pinfunction "QD_3") (pintype "tri_state"))
      (node (ref "R140") (pin "1") (pinfunction "1_1") (pintype "passive"))
    )
    (net (code "162") (name "Net-(IC18A-QE)") (class "Default")
      (node (ref "IC18") (pin "4") (pinfunction "QE_4") (pintype "tri_state"))
      (node (ref "R141") (pin "1") (pinfunction "1_1") (pintype "passive"))
    )
    (net (code "163") (name "Net-(IC18A-QF)") (class "Default")
      (node (ref "IC18") (pin "5") (pinfunction "QF_5") (pintype "tri_state"))
      (node (ref "R142") (pin "1") (pinfunction "1_1") (pintype "passive"))
    )
    (net (code "164") (name "Net-(IC18A-QG)") (class "Default")
      (node (ref "IC18") (pin "6") (pinfunction "QG_6") (pintype "tri_state"))
      (node (ref "R143") (pin "1") (pinfunction "1_1") (pintype "passive"))
    )
    (net (code "165") (name "Net-(IC18A-QH)") (class "Default")
      (node (ref "IC18") (pin "7") (pinfunction "QH_7") (pintype "tri_state"))
      (node (ref "R144") (pin "1") (pinfunction "1_1") (pintype "passive"))
    )
    (net (code "166") (name "Net-(IC18A-QH*)") (class "Default")
      (node (ref "IC18") (pin "9") (pinfunction "QH*_9") (pintype "tri_state"))
      (node (ref "PIN-9") (pin "TP") (pinfunction "TP_TP") (pintype "input"))
    )
    (net (code "167") (name "Net-(LED2-PadA)") (class "Default")
      (node (ref "LED2") (pin "A") (pinfunction "A_A") (pintype "passive"))
      (node (ref "R2") (pin "2") (pinfunction "2_2") (pintype "passive"))
    )
    (net (code "168") (name "Net-(LED3-PadA)") (class "Default")
      (node (ref "LED3") (pin "A") (pinfunction "A_A") (pintype "passive"))
      (node (ref "R3") (pin "2") (pinfunction "2_2") (pintype "passive"))
    )
    (net (code "169") (name "Net-(LED4-PadA)") (class "Default")
      (node (ref "LED4") (pin "A") (pinfunction "A_A") (pintype "passive"))
      (node (ref "R4") (pin "2") (pinfunction "2_2") (pintype "passive"))
    )
    (net (code "170") (name "Net-(LED5-PadA)") (class "Default")
      (node (ref "LED5") (pin "A") (pinfunction "A_A") (pintype "passive"))
      (node (ref "R5") (pin "2") (pinfunction "2_2") (pintype "passive"))
    )
    (net (code "171") (name "Net-(LED6-PadA)") (class "Default")
      (node (ref "LED6") (pin "A") (pinfunction "A_A") (pintype "passive"))
      (node (ref "R6") (pin "2") (pinfunction "2_2") (pintype "passive"))
    )
    (net (code "172") (name "Net-(LED7-PadA)") (class "Default")
      (node (ref "LED7") (pin "A") (pinfunction "A_A") (pintype "passive"))
      (node (ref "R7") (pin "2") (pinfunction "2_2") (pintype "passive"))
    )
    (net (code "173") (name "Net-(LED8-PadA)") (class "Default")
      (node (ref "LED8") (pin "A") (pinfunction "A_A") (pintype "passive"))
      (node (ref "R8") (pin "2") (pinfunction "2_2") (pintype "passive"))
    )
    (net (code "174") (name "Net-(LED9-PadA)") (class "Default")
      (node (ref "LED9") (pin "A") (pinfunction "A_A") (pintype "passive"))
      (node (ref "R9") (pin "2") (pinfunction "2_2") (pintype "passive"))
    )
    (net (code "175") (name "Net-(LED10-PadA)") (class "Default")
      (node (ref "LED10") (pin "A") (pinfunction "A_A") (pintype "passive"))
      (node (ref "R10") (pin "2") (pinfunction "2_2") (pintype "passive"))
    )
    (net (code "176") (name "Net-(LED11-PadA)") (class "Default")
      (node (ref "LED11") (pin "A") (pinfunction "A_A") (pintype "passive"))
      (node (ref "R11") (pin "2") (pinfunction "2_2") (pintype "passive"))
    )
    (net (code "177") (name "Net-(LED12-PadA)") (class "Default")
      (node (ref "LED12") (pin "A") (pinfunction "A_A") (pintype "passive"))
      (node (ref "R12") (pin "2") (pinfunction "2_2") (pintype "passive"))
    )
    (net (code "178") (name "Net-(LED13-PadA)") (class "Default")
      (node (ref "LED13") (pin "A") (pinfunction "A_A") (pintype "passive"))
      (node (ref "R13") (pin "2") (pinfunction "2_2") (pintype "passive"))
    )
    (net (code "179") (name "Net-(LED14-PadA)") (class "Default")
      (node (ref "LED14") (pin "A") (pinfunction "A_A") (pintype "passive"))
      (node (ref "R14") (pin "2") (pinfunction "2_2") (pintype "passive"))
    )
    (net (code "180") (name "Net-(LED15-PadA)") (class "Default")
      (node (ref "LED15") (pin "A") (pinfunction "A_A") (pintype "passive"))
      (node (ref "R15") (pin "2") (pinfunction "2_2") (pintype "passive"))
    )
    (net (code "181") (name "Net-(LED16-PadA)") (class "Default")
      (node (ref "LED16") (pin "A") (pinfunction "A_A") (pintype "passive"))
      (node (ref "R16") (pin "2") (pinfunction "2_2") (pintype "passive"))
    )
    (net (code "182") (name "Net-(LED17-PadA)") (class "Default")
      (node (ref "LED17") (pin "A") (pinfunction "A_A") (pintype "passive"))
      (node (ref "R17") (pin "2") (pinfunction "2_2") (pintype "passive"))
    )
    (net (code "183") (name "Net-(LED18-PadA)") (class "Default")
      (node (ref "LED18") (pin "A") (pinfunction "A_A") (pintype "passive"))
      (node (ref "R18") (pin "2") (pinfunction "2_2") (pintype "passive"))
    )
    (net (code "184") (name "Net-(LED19-PadA)") (class "Default")
      (node (ref "LED19") (pin "A") (pinfunction "A_A") (pintype "passive"))
      (node (ref "R19") (pin "2") (pinfunction "2_2") (pintype "passive"))
    )
    (net (code "185") (name "Net-(LED20-PadA)") (class "Default")
      (node (ref "LED20") (pin "A") (pinfunction "A_A") (pintype "passive"))
      (node (ref "R20") (pin "2") (pinfunction "2_2") (pintype "passive"))
    )
    (net (code "186") (name "Net-(LED21-PadA)") (class "Default")
      (node (ref "LED21") (pin "A") (pinfunction "A_A") (pintype "passive"))
      (node (ref "R21") (pin "2") (pinfunction "2_2") (pintype "passive"))
    )
    (net (code "187") (name "Net-(LED22-PadA)") (class "Default")
      (node (ref "LED22") (pin "A") (pinfunction "A_A") (pintype "passive"))
      (node (ref "R22") (pin "2") (pinfunction "2_2") (pintype "passive"))
    )
    (net (code "188") (name "Net-(LED23-PadA)") (class "Default")
      (node (ref "LED23") (pin "A") (pinfunction "A_A") (pintype "passive"))
      (node (ref "R23") (pin "2") (pinfunction "2_2") (pintype "passive"))
    )
    (net (code "189") (name "Net-(LED24-PadA)") (class "Default")
      (node (ref "LED24") (pin "A") (pinfunction "A_A") (pintype "passive"))
      (node (ref "R24") (pin "2") (pinfunction "2_2") (pintype "passive"))
    )
    (net (code "190") (name "Net-(LED25-PadA)") (class "Default")
      (node (ref "LED25") (pin "A") (pinfunction "A_A") (pintype "passive"))
      (node (ref "R25") (pin "2") (pinfunction "2_2") (pintype "passive"))
    )
    (net (code "191") (name "Net-(LED26-PadA)") (class "Default")
      (node (ref "LED26") (pin "A") (pinfunction "A_A") (pintype "passive"))
      (node (ref "R26") (pin "2") (pinfunction "2_2") (pintype "passive"))
    )
    (net (code "192") (name "Net-(LED27-PadA)") (class "Default")
      (node (ref "LED27") (pin "A") (pinfunction "A_A") (pintype "passive"))
      (node (ref "R27") (pin "2") (pinfunction "2_2") (pintype "passive"))
    )
    (net (code "193") (name "Net-(LED28-PadA)") (class "Default")
      (node (ref "LED28") (pin "A") (pinfunction "A_A") (pintype "passive"))
      (node (ref "R28") (pin "2") (pinfunction "2_2") (pintype "passive"))
    )
    (net (code "194") (name "Net-(LED29-PadA)") (class "Default")
      (node (ref "LED29") (pin "A") (pinfunction "A_A") (pintype "passive"))
      (node (ref "R29") (pin "2") (pinfunction "2_2") (pintype "passive"))
    )
    (net (code "195") (name "Net-(LED30-PadA)") (class "Default")
      (node (ref "LED30") (pin "A") (pinfunction "A_A") (pintype "passive"))
      (node (ref "R30") (pin "2") (pinfunction "2_2") (pintype "passive"))
    )
    (net (code "196") (name "Net-(LED31-PadA)") (class "Default")
      (node (ref "LED31") (pin "A") (pinfunction "A_A") (pintype "passive"))
      (node (ref "R31") (pin "2") (pinfunction "2_2") (pintype "passive"))
    )
    (net (code "197") (name "Net-(LED32-PadA)") (class "Default")
      (node (ref "LED32") (pin "A") (pinfunction "A_A") (pintype "passive"))
      (node (ref "R32") (pin "2") (pinfunction "2_2") (pintype "passive"))
    )
    (net (code "198") (name "Net-(LED33-PadA)") (class "Default")
      (node (ref "LED33") (pin "A") (pinfunction "A_A") (pintype "passive"))
      (node (ref "R33") (pin "2") (pinfunction "2_2") (pintype "passive"))
    )
    (net (code "199") (name "Net-(LED34-PadA)") (class "Default")
      (node (ref "LED34") (pin "A") (pinfunction "A_A") (pintype "passive"))
      (node (ref "R34") (pin "2") (pinfunction "2_2") (pintype "passive"))
    )
    (net (code "200") (name "Net-(LED35-PadA)") (class "Default")
      (node (ref "LED35") (pin "A") (pinfunction "A_A") (pintype "passive"))
      (node (ref "R35") (pin "2") (pinfunction "2_2") (pintype "passive"))
    )
    (net (code "201") (name "Net-(LED36-PadA)") (class "Default")
      (node (ref "LED36") (pin "A") (pinfunction "A_A") (pintype "passive"))
      (node (ref "R36") (pin "2") (pinfunction "2_2") (pintype "passive"))
    )
    (net (code "202") (name "Net-(LED37-PadA)") (class "Default")
      (node (ref "LED37") (pin "A") (pinfunction "A_A") (pintype "passive"))
      (node (ref "R37") (pin "2") (pinfunction "2_2") (pintype "passive"))
    )
    (net (code "203") (name "Net-(LED38-PadA)") (class "Default")
      (node (ref "LED38") (pin "A") (pinfunction "A_A") (pintype "passive"))
      (node (ref "R38") (pin "2") (pinfunction "2_2") (pintype "passive"))
    )
    (net (code "204") (name "Net-(LED39-PadA)") (class "Default")
      (node (ref "LED39") (pin "A") (pinfunction "A_A") (pintype "passive"))
      (node (ref "R39") (pin "2") (pinfunction "2_2") (pintype "passive"))
    )
    (net (code "205") (name "Net-(LED40-PadA)") (class "Default")
      (node (ref "LED40") (pin "A") (pinfunction "A_A") (pintype "passive"))
      (node (ref "R40") (pin "2") (pinfunction "2_2") (pintype "passive"))
    )
    (net (code "206") (name "Net-(LED41-PadA)") (class "Default")
      (node (ref "LED41") (pin "A") (pinfunction "A_A") (pintype "passive"))
      (node (ref "R41") (pin "2") (pinfunction "2_2") (pintype "passive"))
    )
    (net (code "207") (name "Net-(LED42-PadA)") (class "Default")
      (node (ref "LED42") (pin "A") (pinfunction "A_A") (pintype "passive"))
      (node (ref "R42") (pin "2") (pinfunction "2_2") (pintype "passive"))
    )
    (net (code "208") (name "Net-(LED43-PadA)") (class "Default")
      (node (ref "LED43") (pin "A") (pinfunction "A_A") (pintype "passive"))
      (node (ref "R43") (pin "2") (pinfunction "2_2") (pintype "passive"))
    )
    (net (code "209") (name "Net-(LED44-PadA)") (class "Default")
      (node (ref "LED44") (pin "A") (pinfunction "A_A") (pintype "passive"))
      (node (ref "R44") (pin "2") (pinfunction "2_2") (pintype "passive"))
    )
    (net (code "210") (name "Net-(LED45-PadA)") (class "Default")
      (node (ref "LED45") (pin "A") (pinfunction "A_A") (pintype "passive"))
      (node (ref "R45") (pin "2") (pinfunction "2_2") (pintype "passive"))
    )
    (net (code "211") (name "Net-(LED46-PadA)") (class "Default")
      (node (ref "LED46") (pin "A") (pinfunction "A_A") (pintype "passive"))
      (node (ref "R46") (pin "2") (pinfunction "2_2") (pintype "passive"))
    )
    (net (code "212") (name "Net-(LED47-PadA)") (class "Default")
      (node (ref "LED47") (pin "A") (pinfunction "A_A") (pintype "passive"))
      (node (ref "R47") (pin "2") (pinfunction "2_2") (pintype "passive"))
    )
    (net (code "213") (name "Net-(LED48-PadA)") (class "Default")
      (node (ref "LED48") (pin "A") (pinfunction "A_A") (pintype "passive"))
      (node (ref "R48") (pin "2") (pinfunction "2_2") (pintype "passive"))
    )
    (net (code "214") (name "Net-(LED49-PadA)") (class "Default")
      (node (ref "LED49") (pin "A") (pinfunction "A_A") (pintype "passive"))
      (node (ref "R49") (pin "2") (pinfunction "2_2") (pintype "passive"))
    )
    (net (code "215") (name "Net-(LED50-PadA)") (class "Default")
      (node (ref "LED50") (pin "A") (pinfunction "A_A") (pintype "passive"))
      (node (ref "R50") (pin "2") (pinfunction "2_2") (pintype "passive"))
    )
    (net (code "216") (name "Net-(LED51-PadA)") (class "Default")
      (node (ref "LED51") (pin "A") (pinfunction "A_A") (pintype "passive"))
      (node (ref "R51") (pin "2") (pinfunction "2_2") (pintype "passive"))
    )
    (net (code "217") (name "Net-(LED52-PadA)") (class "Default")
      (node (ref "LED52") (pin "A") (pinfunction "A_A") (pintype "passive"))
      (node (ref "R52") (pin "2") (pinfunction "2_2") (pintype "passive"))
    )
    (net (code "218") (name "Net-(LED53-PadA)") (class "Default")
      (node (ref "LED53") (pin "A") (pinfunction "A_A") (pintype "passive"))
      (node (ref "R53") (pin "2") (pinfunction "2_2") (pintype "passive"))
    )
    (net (code "219") (name "Net-(LED54-PadA)") (class "Default")
      (node (ref "LED54") (pin "A") (pinfunction "A_A") (pintype "passive"))
      (node (ref "R54") (pin "2") (pinfunction "2_2") (pintype "passive"))
    )
    (net (code "220") (name "Net-(LED55-PadA)") (class "Default")
      (node (ref "LED55") (pin "A") (pinfunction "A_A") (pintype "passive"))
      (node (ref "R55") (pin "2") (pinfunction "2_2") (pintype "passive"))
    )
    (net (code "221") (name "Net-(LED56-PadA)") (class "Default")
      (node (ref "LED56") (pin "A") (pinfunction "A_A") (pintype "passive"))
      (node (ref "R56") (pin "2") (pinfunction "2_2") (pintype "passive"))
    )
    (net (code "222") (name "Net-(LED57-PadA)") (class "Default")
      (node (ref "LED57") (pin "A") (pinfunction "A_A") (pintype "passive"))
      (node (ref "R57") (pin "2") (pinfunction "2_2") (pintype "passive"))
    )
    (net (code "223") (name "Net-(LED58-PadA)") (class "Default")
      (node (ref "LED58") (pin "A") (pinfunction "A_A") (pintype "passive"))
      (node (ref "R58") (pin "2") (pinfunction "2_2") (pintype "passive"))
    )
    (net (code "224") (name "Net-(LED59-PadA)") (class "Default")
      (node (ref "LED59") (pin "A") (pinfunction "A_A") (pintype "passive"))
      (node (ref "R59") (pin "2") (pinfunction "2_2") (pintype "passive"))
    )
    (net (code "225") (name "Net-(LED60-PadA)") (class "Default")
      (node (ref "LED60") (pin "A") (pinfunction "A_A") (pintype "passive"))
      (node (ref "R60") (pin "2") (pinfunction "2_2") (pintype "passive"))
    )
    (net (code "226") (name "Net-(LED61-PadA)") (class "Default")
      (node (ref "LED61") (pin "A") (pinfunction "A_A") (pintype "passive"))
      (node (ref "R61") (pin "2") (pinfunction "2_2") (pintype "passive"))
    )
    (net (code "227") (name "Net-(LED62-PadA)") (class "Default")
      (node (ref "LED62") (pin "A") (pinfunction "A_A") (pintype "passive"))
      (node (ref "R62") (pin "2") (pinfunction "2_2") (pintype "passive"))
    )
    (net (code "228") (name "Net-(LED63-PadA)") (class "Default")
      (node (ref "LED63") (pin "A") (pinfunction "A_A") (pintype "passive"))
      (node (ref "R63") (pin "2") (pinfunction "2_2") (pintype "passive"))
    )
    (net (code "229") (name "Net-(LED64-PadA)") (class "Default")
      (node (ref "LED64") (pin "A") (pinfunction "A_A") (pintype "passive"))
      (node (ref "R64") (pin "2") (pinfunction "2_2") (pintype "passive"))
    )
    (net (code "230") (name "Net-(LED65-PadA)") (class "Default")
      (node (ref "LED65") (pin "A") (pinfunction "A_A") (pintype "passive"))
      (node (ref "R65") (pin "2") (pinfunction "2_2") (pintype "passive"))
    )
    (net (code "231") (name "Net-(LED66-PadA)") (class "Default")
      (node (ref "LED66") (pin "A") (pinfunction "A_A") (pintype "passive"))
      (node (ref "R66") (pin "2") (pinfunction "2_2") (pintype "passive"))
    )
    (net (code "232") (name "Net-(LED67-PadA)") (class "Default")
      (node (ref "LED67") (pin "A") (pinfunction "A_A") (pintype "passive"))
      (node (ref "R67") (pin "2") (pinfunction "2_2") (pintype "passive"))
    )
    (net (code "233") (name "Net-(LED68-PadA)") (class "Default")
      (node (ref "LED68") (pin "A") (pinfunction "A_A") (pintype "passive"))
      (node (ref "R68") (pin "2") (pinfunction "2_2") (pintype "passive"))
    )
    (net (code "234") (name "Net-(LED69-PadA)") (class "Default")
      (node (ref "LED69") (pin "A") (pinfunction "A_A") (pintype "passive"))
      (node (ref "R69") (pin "2") (pinfunction "2_2") (pintype "passive"))
    )
    (net (code "235") (name "Net-(LED70-PadA)") (class "Default")
      (node (ref "LED70") (pin "A") (pinfunction "A_A") (pintype "passive"))
      (node (ref "R70") (pin "2") (pinfunction "2_2") (pintype "passive"))
    )
    (net (code "236") (name "Net-(LED71-PadA)") (class "Default")
      (node (ref "LED71") (pin "A") (pinfunction "A_A") (pintype "passive"))
      (node (ref "R71") (pin "2") (pinfunction "2_2") (pintype "passive"))
    )
    (net (code "237") (name "Net-(LED72-PadA)") (class "Default")
      (node (ref "LED72") (pin "A") (pinfunction "A_A") (pintype "passive"))
      (node (ref "R72") (pin "2") (pinfunction "2_2") (pintype "passive"))
    )
    (net (code "238") (name "Net-(LED73-PadA)") (class "Default")
      (node (ref "LED73") (pin "A") (pinfunction "A_A") (pintype "passive"))
      (node (ref "R73") (pin "2") (pinfunction "2_2") (pintype "passive"))
    )
    (net (code "239") (name "Net-(LED74-PadA)") (class "Default")
      (node (ref "LED74") (pin "A") (pinfunction "A_A") (pintype "passive"))
      (node (ref "R74") (pin "2") (pinfunction "2_2") (pintype "passive"))
    )
    (net (code "240") (name "Net-(LED75-PadA)") (class "Default")
      (node (ref "LED75") (pin "A") (pinfunction "A_A") (pintype "passive"))
      (node (ref "R75") (pin "2") (pinfunction "2_2") (pintype "passive"))
    )
    (net (code "241") (name "Net-(LED76-PadA)") (class "Default")
      (node (ref "LED76") (pin "A") (pinfunction "A_A") (pintype "passive"))
      (node (ref "R76") (pin "2") (pinfunction "2_2") (pintype "passive"))
    )
    (net (code "242") (name "Net-(LED77-PadA)") (class "Default")
      (node (ref "LED77") (pin "A") (pinfunction "A_A") (pintype "passive"))
      (node (ref "R77") (pin "2") (pinfunction "2_2") (pintype "passive"))
    )
    (net (code "243") (name "Net-(LED78-PadA)") (class "Default")
      (node (ref "LED78") (pin "A") (pinfunction "A_A") (pintype "passive"))
      (node (ref "R78") (pin "2") (pinfunction "2_2") (pintype "passive"))
    )
    (net (code "244") (name "Net-(LED79-PadA)") (class "Default")
      (node (ref "LED79") (pin "A") (pinfunction "A_A") (pintype "passive"))
      (node (ref "R79") (pin "2") (pinfunction "2_2") (pintype "passive"))
    )
    (net (code "245") (name "Net-(LED80-PadA)") (class "Default")
      (node (ref "LED80") (pin "A") (pinfunction "A_A") (pintype "passive"))
      (node (ref "R80") (pin "2") (pinfunction "2_2") (pintype "passive"))
    )
    (net (code "246") (name "Net-(LED81-PadA)") (class "Default")
      (node (ref "LED81") (pin "A") (pinfunction "A_A") (pintype "passive"))
      (node (ref "R81") (pin "2") (pinfunction "2_2") (pintype "passive"))
    )
    (net (code "247") (name "Net-(LED82-PadA)") (class "Default")
      (node (ref "LED82") (pin "A") (pinfunction "A_A") (pintype "passive"))
      (node (ref "R82") (pin "2") (pinfunction "2_2") (pintype "passive"))
    )
    (net (code "248") (name "Net-(LED83-PadA)") (class "Default")
      (node (ref "LED83") (pin "A") (pinfunction "A_A") (pintype "passive"))
      (node (ref "R83") (pin "2") (pinfunction "2_2") (pintype "passive"))
    )
    (net (code "249") (name "Net-(LED84-PadA)") (class "Default")
      (node (ref "LED84") (pin "A") (pinfunction "A_A") (pintype "passive"))
      (node (ref "R84") (pin "2") (pinfunction "2_2") (pintype "passive"))
    )
    (net (code "250") (name "Net-(LED85-PadA)") (class "Default")
      (node (ref "LED85") (pin "A") (pinfunction "A_A") (pintype "passive"))
      (node (ref "R85") (pin "2") (pinfunction "2_2") (pintype "passive"))
    )
    (net (code "251") (name "Net-(LED86-PadA)") (class "Default")
      (node (ref "LED86") (pin "A") (pinfunction "A_A") (pintype "passive"))
      (node (ref "R86") (pin "2") (pinfunction "2_2") (pintype "passive"))
    )
    (net (code "252") (name "Net-(LED87-PadA)") (class "Default")
      (node (ref "LED87") (pin "A") (pinfunction "A_A") (pintype "passive"))
      (node (ref "R87") (pin "2") (pinfunction "2_2") (pintype "passive"))
    )
    (net (code "253") (name "Net-(LED88-PadA)") (class "Default")
      (node (ref "LED88") (pin "A") (pinfunction "A_A") (pintype "passive"))
      (node (ref "R88") (pin "2") (pinfunction "2_2") (pintype "passive"))
    )
    (net (code "254") (name "Net-(LED89-PadA)") (class "Default")
      (node (ref "LED89") (pin "A") (pinfunction "A_A") (pintype "passive"))
      (node (ref "R89") (pin "2") (pinfunction "2_2") (pintype "passive"))
    )
    (net (code "255") (name "Net-(LED90-PadA)") (class "Default")
      (node (ref "LED90") (pin "A") (pinfunction "A_A") (pintype "passive"))
      (node (ref "R90") (pin "2") (pinfunction "2_2") (pintype "passive"))
    )
    (net (code "256") (name "Net-(LED91-PadA)") (class "Default")
      (node (ref "LED91") (pin "A") (pinfunction "A_A") (pintype "passive"))
      (node (ref "R91") (pin "2") (pinfunction "2_2") (pintype "passive"))
    )
    (net (code "257") (name "Net-(LED92-PadA)") (class "Default")
      (node (ref "LED92") (pin "A") (pinfunction "A_A") (pintype "passive"))
      (node (ref "R92") (pin "2") (pinfunction "2_2") (pintype "passive"))
    )
    (net (code "258") (name "Net-(LED93-PadA)") (class "Default")
      (node (ref "LED93") (pin "A") (pinfunction "A_A") (pintype "passive"))
      (node (ref "R93") (pin "2") (pinfunction "2_2") (pintype "passive"))
    )
    (net (code "259") (name "Net-(LED94-PadA)") (class "Default")
      (node (ref "LED94") (pin "A") (pinfunction "A_A") (pintype "passive"))
      (node (ref "R94") (pin "2") (pinfunction "2_2") (pintype "passive"))
    )
    (net (code "260") (name "Net-(LED95-PadA)") (class "Default")
      (node (ref "LED95") (pin "A") (pinfunction "A_A") (pintype "passive"))
      (node (ref "R95") (pin "2") (pinfunction "2_2") (pintype "passive"))
    )
    (net (code "261") (name "Net-(LED96-PadA)") (class "Default")
      (node (ref "LED96") (pin "A") (pinfunction "A_A") (pintype "passive"))
      (node (ref "R96") (pin "2") (pinfunction "2_2") (pintype "passive"))
    )
    (net (code "262") (name "Net-(LED97-PadA)") (class "Default")
      (node (ref "LED97") (pin "A") (pinfunction "A_A") (pintype "passive"))
      (node (ref "R97") (pin "2") (pinfunction "2_2") (pintype "passive"))
    )
    (net (code "263") (name "Net-(LED98-PadA)") (class "Default")
      (node (ref "LED98") (pin "A") (pinfunction "A_A") (pintype "passive"))
      (node (ref "R98") (pin "2") (pinfunction "2_2") (pintype "passive"))
    )
    (net (code "264") (name "Net-(LED99-PadA)") (class "Default")
      (node (ref "LED99") (pin "A") (pinfunction "A_A") (pintype "passive"))
      (node (ref "R99") (pin "2") (pinfunction "2_2") (pintype "passive"))
    )
    (net (code "265") (name "Net-(LED100-PadA)") (class "Default")
      (node (ref "LED100") (pin "A") (pinfunction "A_A") (pintype "passive"))
      (node (ref "R100") (pin "2") (pinfunction "2_2") (pintype "passive"))
    )
    (net (code "266") (name "Net-(LED101-PadA)") (class "Default")
      (node (ref "LED101") (pin "A") (pinfunction "A_A") (pintype "passive"))
      (node (ref "R101") (pin "2") (pinfunction "2_2") (pintype "passive"))
    )
    (net (code "267") (name "Net-(LED102-PadA)") (class "Default")
      (node (ref "LED102") (pin "A") (pinfunction "A_A") (pintype "passive"))
      (node (ref "R102") (pin "2") (pinfunction "2_2") (pintype "passive"))
    )
    (net (code "268") (name "Net-(LED103-PadA)") (class "Default")
      (node (ref "LED103") (pin "A") (pinfunction "A_A") (pintype "passive"))
      (node (ref "R103") (pin "2") (pinfunction "2_2") (pintype "passive"))
    )
    (net (code "269") (name "Net-(LED104-PadA)") (class "Default")
      (node (ref "LED104") (pin "A") (pinfunction "A_A") (pintype "passive"))
      (node (ref "R104") (pin "2") (pinfunction "2_2") (pintype "passive"))
    )
    (net (code "270") (name "Net-(LED105-PadA)") (class "Default")
      (node (ref "LED105") (pin "A") (pinfunction "A_A") (pintype "passive"))
      (node (ref "R105") (pin "2") (pinfunction "2_2") (pintype "passive"))
    )
    (net (code "271") (name "Net-(LED106-PadA)") (class "Default")
      (node (ref "LED106") (pin "A") (pinfunction "A_A") (pintype "passive"))
      (node (ref "R106") (pin "2") (pinfunction "2_2") (pintype "passive"))
    )
    (net (code "272") (name "Net-(LED107-PadA)") (class "Default")
      (node (ref "LED107") (pin "A") (pinfunction "A_A") (pintype "passive"))
      (node (ref "R107") (pin "2") (pinfunction "2_2") (pintype "passive"))
    )
    (net (code "273") (name "Net-(LED108-PadA)") (class "Default")
      (node (ref "LED108") (pin "A") (pinfunction "A_A") (pintype "passive"))
      (node (ref "R108") (pin "2") (pinfunction "2_2") (pintype "passive"))
    )
    (net (code "274") (name "Net-(LED109-PadA)") (class "Default")
      (node (ref "LED109") (pin "A") (pinfunction "A_A") (pintype "passive"))
      (node (ref "R109") (pin "2") (pinfunction "2_2") (pintype "passive"))
    )
    (net (code "275") (name "Net-(LED110-PadA)") (class "Default")
      (node (ref "LED110") (pin "A") (pinfunction "A_A") (pintype "passive"))
      (node (ref "R110") (pin "2") (pinfunction "2_2") (pintype "passive"))
    )
    (net (code "276") (name "Net-(LED111-PadA)") (class "Default")
      (node (ref "LED111") (pin "A") (pinfunction "A_A") (pintype "passive"))
      (node (ref "R111") (pin "2") (pinfunction "2_2") (pintype "passive"))
    )
    (net (code "277") (name "Net-(LED112-PadA)") (class "Default")
      (node (ref "LED112") (pin "A") (pinfunction "A_A") (pintype "passive"))
      (node (ref "R112") (pin "2") (pinfunction "2_2") (pintype "passive"))
    )
    (net (code "278") (name "Net-(LED113-PadA)") (class "Default")
      (node (ref "LED113") (pin "A") (pinfunction "A_A") (pintype "passive"))
      (node (ref "R113") (pin "2") (pinfunction "2_2") (pintype "passive"))
    )
    (net (code "279") (name "Net-(LED114-PadA)") (class "Default")
      (node (ref "LED114") (pin "A") (pinfunction "A_A") (pintype "passive"))
      (node (ref "R114") (pin "2") (pinfunction "2_2") (pintype "passive"))
    )
    (net (code "280") (name "Net-(LED115-PadA)") (class "Default")
      (node (ref "LED115") (pin "A") (pinfunction "A_A") (pintype "passive"))
      (node (ref "R115") (pin "2") (pinfunction "2_2") (pintype "passive"))
    )
    (net (code "281") (name "Net-(LED116-PadA)") (class "Default")
      (node (ref "LED116") (pin "A") (pinfunction "A_A") (pintype "passive"))
      (node (ref "R116") (pin "2") (pinfunction "2_2") (pintype "passive"))
    )
    (net (code "282") (name "Net-(LED117-PadA)") (class "Default")
      (node (ref "LED117") (pin "A") (pinfunction "A_A") (pintype "passive"))
      (node (ref "R117") (pin "2") (pinfunction "2_2") (pintype "passive"))
    )
    (net (code "283") (name "Net-(LED118-PadA)") (class "Default")
      (node (ref "LED118") (pin "A") (pinfunction "A_A") (pintype "passive"))
      (node (ref "R118") (pin "2") (pinfunction "2_2") (pintype "passive"))
    )
    (net (code "284") (name "Net-(LED119-PadA)") (class "Default")
      (node (ref "LED119") (pin "A") (pinfunction "A_A") (pintype "passive"))
      (node (ref "R119") (pin "2") (pinfunction "2_2") (pintype "passive"))
    )
    (net (code "285") (name "Net-(LED120-PadA)") (class "Default")
      (node (ref "LED120") (pin "A") (pinfunction "A_A") (pintype "passive"))
      (node (ref "R120") (pin "2") (pinfunction "2_2") (pintype "passive"))
    )
    (net (code "286") (name "Net-(LED121-PadA)") (class "Default")
      (node (ref "LED121") (pin "A") (pinfunction "A_A") (pintype "passive"))
      (node (ref "R121") (pin "2") (pinfunction "2_2") (pintype "passive"))
    )
    (net (code "287") (name "Net-(LED122-PadA)") (class "Default")
      (node (ref "LED122") (pin "A") (pinfunction "A_A") (pintype "passive"))
      (node (ref "R122") (pin "2") (pinfunction "2_2") (pintype "passive"))
    )
    (net (code "288") (name "Net-(LED123-PadA)") (class "Default")
      (node (ref "LED123") (pin "A") (pinfunction "A_A") (pintype "passive"))
      (node (ref "R123") (pin "2") (pinfunction "2_2") (pintype "passive"))
    )
    (net (code "289") (name "Net-(LED124-PadA)") (class "Default")
      (node (ref "LED124") (pin "A") (pinfunction "A_A") (pintype "passive"))
      (node (ref "R124") (pin "2") (pinfunction "2_2") (pintype "passive"))
    )
    (net (code "290") (name "Net-(LED125-PadA)") (class "Default")
      (node (ref "LED125") (pin "A") (pinfunction "A_A") (pintype "passive"))
      (node (ref "R125") (pin "2") (pinfunction "2_2") (pintype "passive"))
    )
    (net (code "291") (name "Net-(LED126-PadA)") (class "Default")
      (node (ref "LED126") (pin "A") (pinfunction "A_A") (pintype "passive"))
      (node (ref "R126") (pin "2") (pinfunction "2_2") (pintype "passive"))
    )
    (net (code "292") (name "Net-(LED127-PadA)") (class "Default")
      (node (ref "LED127") (pin "A") (pinfunction "A_A") (pintype "passive"))
      (node (ref "R127") (pin "2") (pinfunction "2_2") (pintype "passive"))
    )
    (net (code "293") (name "Net-(LED128-PadA)") (class "Default")
      (node (ref "LED128") (pin "A") (pinfunction "A_A") (pintype "passive"))
      (node (ref "R128") (pin "2") (pinfunction "2_2") (pintype "passive"))
    )
    (net (code "294") (name "Net-(LED129-PadA)") (class "Default")
      (node (ref "LED129") (pin "A") (pinfunction "A_A") (pintype "passive"))
      (node (ref "R129") (pin "2") (pinfunction "2_2") (pintype "passive"))
    )
    (net (code "295") (name "Net-(LED130-PadA)") (class "Default")
      (node (ref "LED130") (pin "A") (pinfunction "A_A") (pintype "passive"))
      (node (ref "R130") (pin "2") (pinfunction "2_2") (pintype "passive"))
    )
    (net (code "296") (name "Net-(LED131-PadA)") (class "Default")
      (node (ref "LED131") (pin "A") (pinfunction "A_A") (pintype "passive"))
      (node (ref "R131") (pin "2") (pinfunction "2_2") (pintype "passive"))
    )
    (net (code "297") (name "Net-(LED132-PadA)") (class "Default")
      (node (ref "LED132") (pin "A") (pinfunction "A_A") (pintype "passive"))
      (node (ref "R132") (pin "2") (pinfunction "2_2") (pintype "passive"))
    )
    (net (code "298") (name "Net-(LED133-PadA)") (class "Default")
      (node (ref "LED133") (pin "A") (pinfunction "A_A") (pintype "passive"))
      (node (ref "R133") (pin "2") (pinfunction "2_2") (pintype "passive"))
    )
    (net (code "299") (name "Net-(LED134-PadA)") (class "Default")
      (node (ref "LED134") (pin "A") (pinfunction "A_A") (pintype "passive"))
      (node (ref "R134") (pin "2") (pinfunction "2_2") (pintype "passive"))
    )
    (net (code "300") (name "Net-(LED135-PadA)") (class "Default")
      (node (ref "LED135") (pin "A") (pinfunction "A_A") (pintype "passive"))
      (node (ref "R135") (pin "2") (pinfunction "2_2") (pintype "passive"))
    )
    (net (code "301") (name "Net-(LED136-PadA)") (class "Default")
      (node (ref "LED136") (pin "A") (pinfunction "A_A") (pintype "passive"))
      (node (ref "R136") (pin "2") (pinfunction "2_2") (pintype "passive"))
    )
    (net (code "302") (name "Net-(LED137-PadA)") (class "Default")
      (node (ref "LED137") (pin "A") (pinfunction "A_A") (pintype "passive"))
      (node (ref "R137") (pin "2") (pinfunction "2_2") (pintype "passive"))
    )
    (net (code "303") (name "Net-(LED138-PadA)") (class "Default")
      (node (ref "LED138") (pin "A") (pinfunction "A_A") (pintype "passive"))
      (node (ref "R138") (pin "2") (pinfunction "2_2") (pintype "passive"))
    )
    (net (code "304") (name "Net-(LED139-PadA)") (class "Default")
      (node (ref "LED139") (pin "A") (pinfunction "A_A") (pintype "passive"))
      (node (ref "R139") (pin "2") (pinfunction "2_2") (pintype "passive"))
    )
    (net (code "305") (name "Net-(LED140-PadA)") (class "Default")
      (node (ref "LED140") (pin "A") (pinfunction "A_A") (pintype "passive"))
      (node (ref "R140") (pin "2") (pinfunction "2_2") (pintype "passive"))
    )
    (net (code "306") (name "Net-(LED141-PadA)") (class "Default")
      (node (ref "LED141") (pin "A") (pinfunction "A_A") (pintype "passive"))
      (node (ref "R141") (pin "2") (pinfunction "2_2") (pintype "passive"))
    )
    (net (code "307") (name "Net-(LED142-PadA)") (class "Default")
      (node (ref "LED142") (pin "A") (pinfunction "A_A") (pintype "passive"))
      (node (ref "R142") (pin "2") (pinfunction "2_2") (pintype "passive"))
    )
    (net (code "308") (name "Net-(LED143-PadA)") (class "Default")
      (node (ref "LED143") (pin "A") (pinfunction "A_A") (pintype "passive"))
      (node (ref "R143") (pin "2") (pinfunction "2_2") (pintype "passive"))
    )
    (net (code "309") (name "Net-(LED144-PadA)") (class "Default")
      (node (ref "LED144") (pin "A") (pinfunction "A_A") (pintype "passive"))
      (node (ref "R144") (pin "2") (pinfunction "2_2") (pintype "passive"))
    )
    (net (code "310") (name "unconnected-(IC1A-QA-Pad15)") (class "Default")
      (node (ref "IC1") (pin "15") (pinfunction "QA_15") (pintype "tri_state"))
    )
    (net (code "311") (name "unconnected-(LED1-C-PadK)") (class "Default")
      (node (ref "LED1") (pin "K") (pinfunction "C_K") (pintype "passive"))
    )
    (net (code "312") (name "unconnected-(LED1-PadA)") (class "Default")
      (node (ref "LED1") (pin "A") (pinfunction "A_A") (pintype "passive"))
    )
  )
)
